# Ice-LogicDeck1.net
KiCad netlist of a schematic drawn in EAGLE
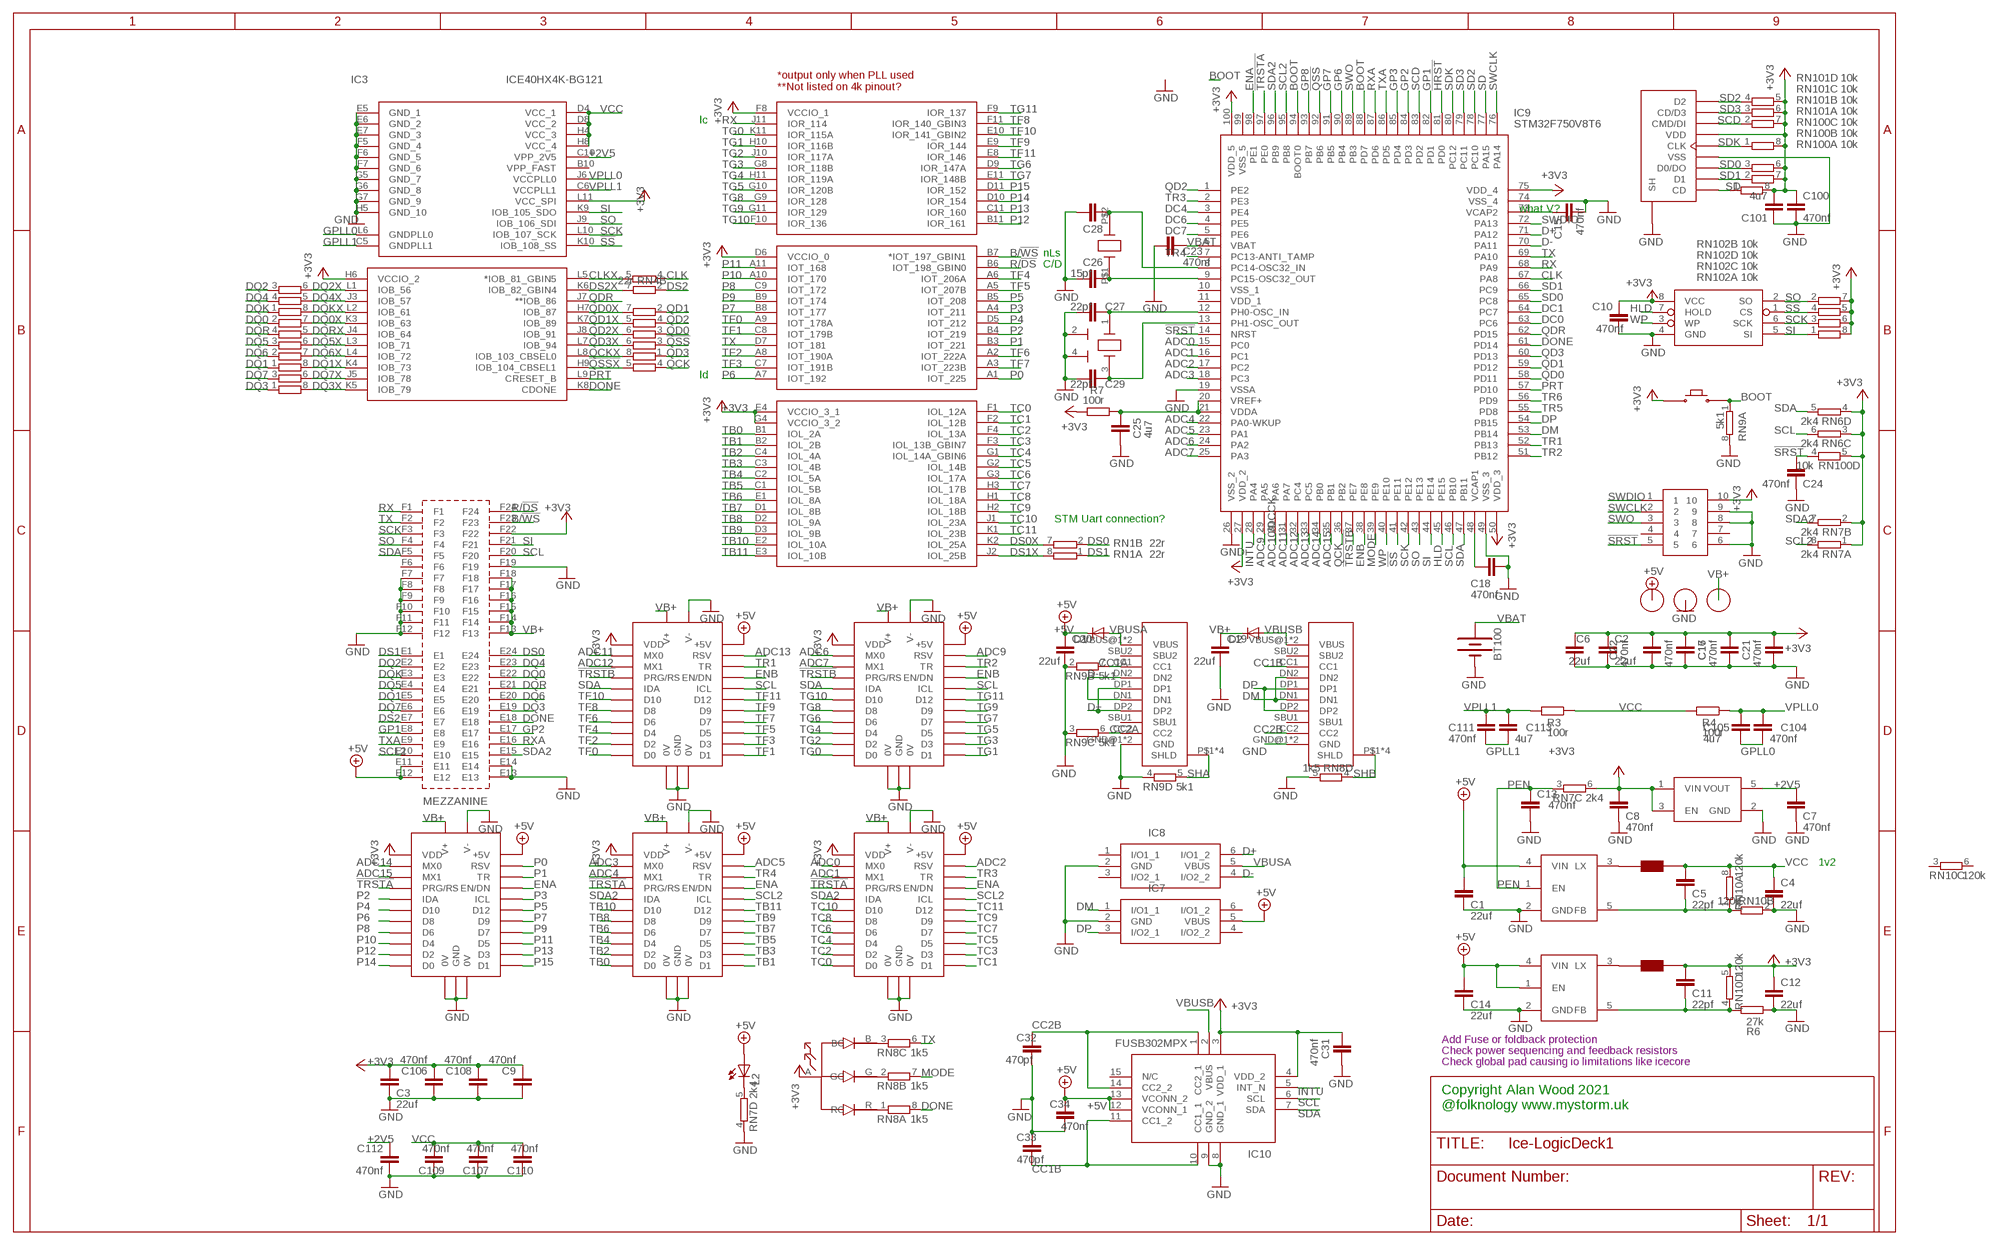
[diagram p0: schematic, sheet 1]

(export (version "E")
  (design (tool "Eeschema 10.0.6"))
  (components
    (comp (ref "BT100")
      (value "BATTERY-20MM_SMD")
      (footprint "eagle-import:BATTCON_20MM")
      (libsource (lib "eagle-import") (part "BATTERY-20MM_SMD"))
    )
    (comp (ref "C1")
      (value "22uf")
      (footprint "eagle-import:C0603")
      (libsource (lib "eagle-import") (part "C-EUC0603"))
    )
    (comp (ref "C2")
      (value "22uf")
      (footprint "eagle-import:C0603")
      (libsource (lib "eagle-import") (part "C-EUC0603"))
    )
    (comp (ref "C3")
      (value "22uf")
      (footprint "eagle-import:C0603")
      (libsource (lib "eagle-import") (part "C-EUC0603"))
    )
    (comp (ref "C4")
      (value "22uf")
      (footprint "eagle-import:C0603")
      (libsource (lib "eagle-import") (part "C-EUC0603"))
    )
    (comp (ref "C5")
      (value "22pf")
      (footprint "eagle-import:C0402")
      (libsource (lib "eagle-import") (part "C-EUC0402"))
    )
    (comp (ref "C6")
      (value "22uf")
      (footprint "eagle-import:C0603")
      (libsource (lib "eagle-import") (part "C-EUC0603"))
    )
    (comp (ref "C7")
      (value "470nf")
      (footprint "eagle-import:C0402")
      (libsource (lib "eagle-import") (part "C-EUC0402"))
    )
    (comp (ref "C8")
      (value "470nf")
      (footprint "eagle-import:C0402")
      (libsource (lib "eagle-import") (part "C-EUC0402"))
    )
    (comp (ref "C9")
      (value "470nf")
      (footprint "eagle-import:C0402")
      (libsource (lib "eagle-import") (part "C-EUC0402"))
    )
    (comp (ref "C10")
      (value "470nf")
      (footprint "eagle-import:C0402")
      (libsource (lib "eagle-import") (part "C-EUC0402"))
    )
    (comp (ref "C11")
      (value "22pf")
      (footprint "eagle-import:C0402")
      (libsource (lib "eagle-import") (part "C-EUC0402"))
    )
    (comp (ref "C12")
      (value "22uf")
      (footprint "eagle-import:C0603")
      (libsource (lib "eagle-import") (part "C-EUC0603"))
    )
    (comp (ref "C13")
      (value "470nf")
      (footprint "eagle-import:C0402")
      (libsource (lib "eagle-import") (part "C-EUC0402"))
    )
    (comp (ref "C14")
      (value "22uf")
      (footprint "eagle-import:C0603")
      (libsource (lib "eagle-import") (part "C-EUC0603"))
    )
    (comp (ref "C15")
      (value "470nf")
      (footprint "eagle-import:C0402")
      (libsource (lib "eagle-import") (part "C-EUC0402"))
    )
    (comp (ref "C16")
      (value "470nf")
      (footprint "eagle-import:C0402")
      (libsource (lib "eagle-import") (part "C-EUC0402"))
    )
    (comp (ref "C17")
      (value "470nf")
      (footprint "eagle-import:C0402")
      (libsource (lib "eagle-import") (part "C-EUC0402"))
    )
    (comp (ref "C18")
      (value "470nf")
      (footprint "eagle-import:C0402")
      (libsource (lib "eagle-import") (part "C-EUC0402"))
    )
    (comp (ref "C19")
      (value "22uf")
      (footprint "eagle-import:C0603")
      (libsource (lib "eagle-import") (part "C-EUC0603"))
    )
    (comp (ref "C20")
      (value "22uf")
      (footprint "eagle-import:C0603")
      (libsource (lib "eagle-import") (part "C-EUC0603"))
    )
    (comp (ref "C21")
      (value "470nf")
      (footprint "eagle-import:C0402")
      (libsource (lib "eagle-import") (part "C-EUC0402"))
    )
    (comp (ref "C22")
      (value "470nf")
      (footprint "eagle-import:C0402")
      (libsource (lib "eagle-import") (part "C-EUC0402"))
    )
    (comp (ref "C23")
      (value "470nf")
      (footprint "eagle-import:C0402")
      (libsource (lib "eagle-import") (part "C-EUC0402"))
    )
    (comp (ref "C24")
      (value "470nf")
      (footprint "eagle-import:C0402")
      (libsource (lib "eagle-import") (part "C-EUC0402"))
    )
    (comp (ref "C25")
      (value "4u7")
      (footprint "eagle-import:C0402")
      (libsource (lib "eagle-import") (part "C-EUC0402"))
    )
    (comp (ref "C26")
      (value "15pf")
      (footprint "eagle-import:C0402")
      (libsource (lib "eagle-import") (part "C-EUC0402"))
    )
    (comp (ref "C27")
      (value "22pf")
      (footprint "eagle-import:C0402")
      (libsource (lib "eagle-import") (part "C-EUC0402"))
    )
    (comp (ref "C28")
      (value "15pf")
      (footprint "eagle-import:C0402")
      (libsource (lib "eagle-import") (part "C-EUC0402"))
    )
    (comp (ref "C29")
      (value "22pf")
      (footprint "eagle-import:C0402")
      (libsource (lib "eagle-import") (part "C-EUC0402"))
    )
    (comp (ref "C31")
      (value "470nf")
      (footprint "eagle-import:C0402")
      (libsource (lib "eagle-import") (part "C-EUC0402"))
    )
    (comp (ref "C32")
      (value "470pf")
      (footprint "eagle-import:C0402")
      (libsource (lib "eagle-import") (part "C-EUC0402"))
    )
    (comp (ref "C33")
      (value "470pf")
      (footprint "eagle-import:C0402")
      (libsource (lib "eagle-import") (part "C-EUC0402"))
    )
    (comp (ref "C34")
      (value "470nf")
      (footprint "eagle-import:C0402")
      (libsource (lib "eagle-import") (part "C-EUC0402"))
    )
    (comp (ref "C100")
      (value "470nf")
      (footprint "eagle-import:C0402")
      (libsource (lib "eagle-import") (part "C-EUC0402"))
    )
    (comp (ref "C101")
      (value "4u7")
      (footprint "eagle-import:C0402")
      (libsource (lib "eagle-import") (part "C-EUC0402"))
    )
    (comp (ref "C104")
      (value "470nf")
      (footprint "eagle-import:C0402")
      (libsource (lib "eagle-import") (part "C-EUC0402"))
    )
    (comp (ref "C105")
      (value "4u7")
      (footprint "eagle-import:C0402")
      (libsource (lib "eagle-import") (part "C-EUC0402"))
    )
    (comp (ref "C106")
      (value "470nf")
      (footprint "eagle-import:C0402")
      (libsource (lib "eagle-import") (part "C-EUC0402"))
    )
    (comp (ref "C107")
      (value "470nf")
      (footprint "eagle-import:C0402")
      (libsource (lib "eagle-import") (part "C-EUC0402"))
    )
    (comp (ref "C108")
      (value "470nf")
      (footprint "eagle-import:C0402")
      (libsource (lib "eagle-import") (part "C-EUC0402"))
    )
    (comp (ref "C109")
      (value "470nf")
      (footprint "eagle-import:C0402")
      (libsource (lib "eagle-import") (part "C-EUC0402"))
    )
    (comp (ref "C110")
      (value "470nf")
      (footprint "eagle-import:C0402")
      (libsource (lib "eagle-import") (part "C-EUC0402"))
    )
    (comp (ref "C111")
      (value "470nf")
      (footprint "eagle-import:C0402")
      (libsource (lib "eagle-import") (part "C-EUC0402"))
    )
    (comp (ref "C112")
      (value "470nf")
      (footprint "eagle-import:C0402")
      (libsource (lib "eagle-import") (part "C-EUC0402"))
    )
    (comp (ref "C113")
      (value "4u7")
      (footprint "eagle-import:C0402")
      (libsource (lib "eagle-import") (part "C-EUC0402"))
    )
    (comp (ref "CN1")
      (value "USB-C-16")
      (footprint "eagle-import:USB-C")
      (libsource (lib "eagle-import") (part "USB-C-16"))
    )
    (comp (ref "CN2")
      (value "USB-C-16")
      (footprint "eagle-import:USB-C")
      (libsource (lib "eagle-import") (part "USB-C-16"))
    )
    (comp (ref "CN3")
      (value "2X5-HEADER")
      (footprint "eagle-import:1.27-2X5-HEADER")
      (libsource (lib "eagle-import") (part "2X5-HEADER"))
    )
    (comp (ref "D1")
      (value "DIODE-SOD123")
      (footprint "eagle-import:SOD123")
      (libsource (lib "eagle-import") (part "DIODE-SOD123"))
    )
    (comp (ref "D2")
      (value "DIODE-SOD123")
      (footprint "eagle-import:SOD123")
      (libsource (lib "eagle-import") (part "DIODE-SOD123"))
    )
    (comp (ref "DFU")
      (value "4X3-RA-BUTTON")
      (footprint "eagle-import:4X3-RA-BUTTON")
      (libsource (lib "eagle-import") (part "4X3-RA-BUTTON"))
    )
    (comp (ref "H1")
      (value "HOLE2.5MM-LARGE")
      (footprint "eagle-import:2M5-LARGE")
      (libsource (lib "eagle-import") (part "HOLE2.5MM-LARGE"))
    )
    (comp (ref "H3")
      (value "HOLE2.5MM-LARGE")
      (footprint "eagle-import:2M5-LARGE")
      (libsource (lib "eagle-import") (part "HOLE2.5MM-LARGE"))
    )
    (comp (ref "H4")
      (value "HOLE2.5MM-LARGE")
      (footprint "eagle-import:2M5-LARGE")
      (libsource (lib "eagle-import") (part "HOLE2.5MM-LARGE"))
    )
    (comp (ref "I1")
      (value "NRS4018")
      (footprint "eagle-import:NRC4018")
      (libsource (lib "eagle-import") (part "NRS4018"))
    )
    (comp (ref "I2")
      (value "NRS4018")
      (footprint "eagle-import:NRC4018")
      (libsource (lib "eagle-import") (part "NRS4018"))
    )
    (comp (ref "IC1")
      (value "AP3429/A")
      (footprint "eagle-import:TSOP-5_SOT23-5")
      (libsource (lib "eagle-import") (part "AP3429/A"))
    )
    (comp (ref "IC2")
      (value "NCP114")
      (footprint "eagle-import:TSOP-5_SOT23-5")
      (libsource (lib "eagle-import") (part "NCP114"))
    )
    (comp (ref "IC3")
      (value "ICE40HX4K-BG121")
      (footprint "eagle-import:BGA121C80P11X11_900X900X110")
      (fields (field (name "MOUSER_PART_NUMBER") "842-ICE40HX4K-BG121"))
      (libsource (lib "eagle-import") (part "ICE40HX4K-BG121"))
    )
    (comp (ref "IC4")
      (value "AT25SDF041A")
      (footprint "eagle-import:SOIC-8-NARROW")
      (libsource (lib "eagle-import") (part "AT25SDF041A"))
    )
    (comp (ref "IC5")
      (value "AP3429/A")
      (footprint "eagle-import:TSOP-5_SOT23-5")
      (libsource (lib "eagle-import") (part "AP3429/A"))
    )
    (comp (ref "IC7")
      (value "USBLC6-2SC6")
      (footprint "eagle-import:SOT95P280X145-6N")
      (fields (field (name "MOUSER_PART_NUMBER") "511-USBLC6-2SC6"))
      (libsource (lib "eagle-import") (part "USBLC6-2SC6"))
    )
    (comp (ref "IC8")
      (value "USBLC6-2SC6")
      (footprint "eagle-import:SOT95P280X145-6N")
      (fields (field (name "MOUSER_PART_NUMBER") "511-USBLC6-2SC6"))
      (libsource (lib "eagle-import") (part "USBLC6-2SC6"))
    )
    (comp (ref "IC9")
      (value "STM32F750V8T6")
      (footprint "eagle-import:QFP50P1600X1600X160-100N")
      (fields (field (name "MOUSER_PART_NUMBER") "511-STM32F750V8T6"))
      (libsource (lib "eagle-import") (part "STM32F750V8T6"))
    )
    (comp (ref "IC10")
      (value "FUSB302MPX")
      (footprint "eagle-import:QFN50P250X250X80-15N")
      (fields (field (name "MOUSER_PART_NUMBER") "512-FUSB302MPX"))
      (libsource (lib "eagle-import") (part "FUSB302MPX"))
    )
    (comp (ref "L1")
      (value "RGB_LED")
      (footprint "eagle-import:RGB_LED_IMM")
      (libsource (lib "eagle-import") (part "RGB_LED"))
    )
    (comp (ref "L2")
      (value "LEDCHIPLED_0805")
      (footprint "eagle-import:CHIPLED_0805")
      (libsource (lib "eagle-import") (part "LEDCHIPLED_0805"))
    )
    (comp (ref "MEZZANINE")
      (value "HYPER-TILECARRIER")
      (footprint "eagle-import:HYPER-TILE")
      (libsource (lib "eagle-import") (part "HYPER-TILECARRIER"))
    )
    (comp (ref "R3")
      (value "100r")
      (footprint "eagle-import:R0402")
      (libsource (lib "eagle-import") (part "R-EU_R0402"))
    )
    (comp (ref "R4")
      (value "100r")
      (footprint "eagle-import:R0402")
      (libsource (lib "eagle-import") (part "R-EU_R0402"))
    )
    (comp (ref "R6")
      (value "27k")
      (footprint "eagle-import:R0402")
      (libsource (lib "eagle-import") (part "R-EU_R0402"))
    )
    (comp (ref "R7")
      (value "100r")
      (footprint "eagle-import:R0402")
      (libsource (lib "eagle-import") (part "R-EU_R0402"))
    )
    (comp (ref "RN1")
      (value "22r")
      (footprint "eagle-import:EXB38V")
      (libsource (lib "eagle-import") (part "4R-NEXB38V"))
    )
    (comp (ref "RN2")
      (value "22r")
      (footprint "eagle-import:EXB38V")
      (libsource (lib "eagle-import") (part "4R-NEXB38V"))
    )
    (comp (ref "RN3")
      (value "22r")
      (footprint "eagle-import:EXB38V")
      (libsource (lib "eagle-import") (part "4R-NEXB38V"))
    )
    (comp (ref "RN4")
      (value "22r")
      (footprint "eagle-import:EXB38V")
      (libsource (lib "eagle-import") (part "4R-NEXB38V"))
    )
    (comp (ref "RN5")
      (value "22r")
      (footprint "eagle-import:EXB38V")
      (libsource (lib "eagle-import") (part "4R-NEXB38V"))
    )
    (comp (ref "RN6")
      (value "2k4")
      (footprint "eagle-import:EXB38V")
      (libsource (lib "eagle-import") (part "4R-NEXB38V"))
    )
    (comp (ref "RN7")
      (value "2k4")
      (footprint "eagle-import:EXB38V")
      (libsource (lib "eagle-import") (part "4R-NEXB38V"))
    )
    (comp (ref "RN8")
      (value "1k5")
      (footprint "eagle-import:EXB38V")
      (libsource (lib "eagle-import") (part "4R-NEXB38V"))
    )
    (comp (ref "RN9")
      (value "5k1")
      (footprint "eagle-import:EXB38V")
      (libsource (lib "eagle-import") (part "4R-NEXB38V"))
    )
    (comp (ref "RN10")
      (value "120k")
      (footprint "eagle-import:EXB38V")
      (libsource (lib "eagle-import") (part "4R-NEXB38V"))
    )
    (comp (ref "RN100")
      (value "10k")
      (footprint "eagle-import:EXB38V")
      (libsource (lib "eagle-import") (part "4R-NEXB38V"))
    )
    (comp (ref "RN101")
      (value "10k")
      (footprint "eagle-import:EXB38V")
      (libsource (lib "eagle-import") (part "4R-NEXB38V"))
    )
    (comp (ref "RN102")
      (value "10k")
      (footprint "eagle-import:EXB38V")
      (libsource (lib "eagle-import") (part "4R-NEXB38V"))
    )
    (comp (ref "SD100")
      (value "TF-15X15")
      (footprint "eagle-import:SDCARD")
      (libsource (lib "eagle-import") (part "TF-15X15"))
    )
    (comp (ref "TILE1")
      (value "UTILE_LPCARRIER_SMD_MALE_1.27")
      (footprint "eagle-import:UTILE_LP")
      (libsource (lib "eagle-import") (part "UTILE_LPCARRIER_SMD_MALE_1.27"))
    )
    (comp (ref "TILE2")
      (value "UTILE_LPCARRIER_SMD_MALE_1.27")
      (footprint "eagle-import:UTILE_LP")
      (libsource (lib "eagle-import") (part "UTILE_LPCARRIER_SMD_MALE_1.27"))
    )
    (comp (ref "TILE3")
      (value "UTILE_LPCARRIER_SMD_MALE_1.27")
      (footprint "eagle-import:UTILE_LP")
      (libsource (lib "eagle-import") (part "UTILE_LPCARRIER_SMD_MALE_1.27"))
    )
    (comp (ref "TILE4")
      (value "UTILE_LPCARRIER_SMD_MALE_1.27")
      (footprint "eagle-import:UTILE_LP")
      (libsource (lib "eagle-import") (part "UTILE_LPCARRIER_SMD_MALE_1.27"))
    )
    (comp (ref "TILE5")
      (value "UTILE_LPCARRIER_SMD_MALE_1.27")
      (footprint "eagle-import:UTILE_LP")
      (libsource (lib "eagle-import") (part "UTILE_LPCARRIER_SMD_MALE_1.27"))
    )
    (comp (ref "Y1")
      (value "12MZ")
      (footprint "eagle-import:CRYSTAL-3.2X2.5")
      (libsource (lib "eagle-import") (part "7M-25"))
    )
    (comp (ref "Y2")
      (value "FC-135")
      (footprint "eagle-import:FC135")
      (libsource (lib "eagle-import") (part "FC-135"))
    )
  )
  (nets
    (net (code "1") (name "+3V3") (class "Default")
      (node (ref "C10") (pin "1") (pinfunction "1_1") (pintype "passive"))
      (node (ref "C100") (pin "1") (pinfunction "1_1") (pintype "passive"))
      (node (ref "C101") (pin "2") (pinfunction "2_2") (pintype "passive"))
      (node (ref "C106") (pin "1") (pinfunction "1_1") (pintype "passive"))
      (node (ref "C108") (pin "1") (pinfunction "1_1") (pintype "passive"))
      (node (ref "C11") (pin "2") (pinfunction "2_2") (pintype "passive"))
      (node (ref "C12") (pin "1") (pinfunction "1_1") (pintype "passive"))
      (node (ref "C16") (pin "2") (pinfunction "2_2") (pintype "passive"))
      (node (ref "C17") (pin "2") (pinfunction "2_2") (pintype "passive"))
      (node (ref "C2") (pin "1") (pinfunction "1_1") (pintype "passive"))
      (node (ref "C21") (pin "2") (pinfunction "2_2") (pintype "passive"))
      (node (ref "C22") (pin "2") (pinfunction "2_2") (pintype "passive"))
      (node (ref "C3") (pin "2") (pinfunction "2_2") (pintype "passive"))
      (node (ref "C31") (pin "2") (pinfunction "2_2") (pintype "passive"))
      (node (ref "C6") (pin "2") (pinfunction "2_2") (pintype "passive"))
      (node (ref "C8") (pin "2") (pinfunction "2_2") (pintype "passive"))
      (node (ref "C9") (pin "1") (pinfunction "1_1") (pintype "passive"))
      (node (ref "CN3") (pin "10") (pinfunction "10_10") (pintype "bidirectional"))
      (node (ref "DFU") (pin "P$1") (pinfunction "P$1_P$1") (pintype "passive"))
      (node (ref "I2") (pin "P$2") (pinfunction "P$2_P$2") (pintype "passive"))
      (node (ref "IC10") (pin "3") (pinfunction "VDD_1_3") (pintype "bidirectional"))
      (node (ref "IC10") (pin "4") (pinfunction "VDD_2_4") (pintype "bidirectional"))
      (node (ref "IC2") (pin "1") (pinfunction "VIN_1") (pintype "power_in"))
      (node (ref "IC2") (pin "3") (pinfunction "EN_3") (pintype "input"))
      (node (ref "IC3") (pin "D6") (pinfunction "VCCIO_0_D6") (pintype "bidirectional"))
      (node (ref "IC3") (pin "E4") (pinfunction "VCCIO_3_1_E4") (pintype "bidirectional"))
      (node (ref "IC3") (pin "F8") (pinfunction "VCCIO_1_F8") (pintype "bidirectional"))
      (node (ref "IC3") (pin "G4") (pinfunction "VCCIO_3_2_G4") (pintype "bidirectional"))
      (node (ref "IC3") (pin "H6") (pinfunction "VCCIO_2_H6") (pintype "bidirectional"))
      (node (ref "IC3") (pin "L11") (pinfunction "VCC_SPI_L11") (pintype "bidirectional"))
      (node (ref "IC4") (pin "8") (pinfunction "VCC_8") (pintype "power_in"))
      (node (ref "IC9") (pin "100") (pinfunction "VDD_5_100") (pintype "bidirectional"))
      (node (ref "IC9") (pin "27") (pinfunction "VDD_2_27") (pintype "bidirectional"))
      (node (ref "IC9") (pin "50") (pinfunction "VDD_3_50") (pintype "bidirectional"))
      (node (ref "IC9") (pin "75") (pinfunction "VDD_4_75") (pintype "bidirectional"))
      (node (ref "L1") (pin "A") (pinfunction "ANODE_A") (pintype "bidirectional"))
      (node (ref "MEZZANINE") (pin "F22") (pinfunction "F22_F22") (pintype "bidirectional"))
      (node (ref "R7") (pin "2") (pinfunction "2_2") (pintype "passive"))
      (node (ref "RN10") (pin "5") (pinfunction "2_5") (pintype "passive"))
      (node (ref "RN100") (pin "5") (pinfunction "2_5") (pintype "passive"))
      (node (ref "RN100") (pin "6") (pinfunction "2_6") (pintype "passive"))
      (node (ref "RN100") (pin "7") (pinfunction "2_7") (pintype "passive"))
      (node (ref "RN100") (pin "8") (pinfunction "2_8") (pintype "passive"))
      (node (ref "RN101") (pin "5") (pinfunction "2_5") (pintype "passive"))
      (node (ref "RN101") (pin "6") (pinfunction "2_6") (pintype "passive"))
      (node (ref "RN101") (pin "7") (pinfunction "2_7") (pintype "passive"))
      (node (ref "RN101") (pin "8") (pinfunction "2_8") (pintype "passive"))
      (node (ref "RN102") (pin "5") (pinfunction "2_5") (pintype "passive"))
      (node (ref "RN102") (pin "6") (pinfunction "2_6") (pintype "passive"))
      (node (ref "RN102") (pin "7") (pinfunction "2_7") (pintype "passive"))
      (node (ref "RN102") (pin "8") (pinfunction "2_8") (pintype "passive"))
      (node (ref "RN6") (pin "3") (pinfunction "1_3") (pintype "passive"))
      (node (ref "RN6") (pin "4") (pinfunction "1_4") (pintype "passive"))
      (node (ref "RN7") (pin "1") (pinfunction "1_1") (pintype "passive"))
      (node (ref "RN7") (pin "2") (pinfunction "1_2") (pintype "passive"))
      (node (ref "RN7") (pin "6") (pinfunction "2_6") (pintype "passive"))
      (node (ref "SD100") (pin "P$6") (pinfunction "VDD_P$6") (pintype "power_in"))
      (node (ref "TILE1") (pin "P$18") (pinfunction "VDD_P$18") (pintype "power_in"))
      (node (ref "TILE2") (pin "P$18") (pinfunction "VDD_P$18") (pintype "power_in"))
      (node (ref "TILE3") (pin "P$18") (pinfunction "VDD_P$18") (pintype "power_in"))
      (node (ref "TILE4") (pin "P$18") (pinfunction "VDD_P$18") (pintype "power_in"))
      (node (ref "TILE5") (pin "P$18") (pinfunction "VDD_P$18") (pintype "power_in"))
    )
    (net (code "2") (name "+5V") (class "Default")
      (node (ref "C1") (pin "2") (pinfunction "2_2") (pintype "passive"))
      (node (ref "C14") (pin "2") (pinfunction "2_2") (pintype "passive"))
      (node (ref "C20") (pin "1") (pinfunction "1_1") (pintype "passive"))
      (node (ref "C34") (pin "2") (pinfunction "2_2") (pintype "passive"))
      (node (ref "D1") (pin "C") (pinfunction "C_C") (pintype "passive"))
      (node (ref "H1") (pin "P$1") (pinfunction "P_P$1") (pintype "bidirectional"))
      (node (ref "IC1") (pin "4") (pinfunction "VIN_4") (pintype "power_in"))
      (node (ref "IC10") (pin "12") (pinfunction "VCONN_1_12") (pintype "bidirectional"))
      (node (ref "IC10") (pin "13") (pinfunction "VCONN_2_13") (pintype "bidirectional"))
      (node (ref "IC5") (pin "1") (pinfunction "EN_1") (pintype "input"))
      (node (ref "IC5") (pin "4") (pinfunction "VIN_4") (pintype "power_in"))
      (node (ref "IC7") (pin "5") (pinfunction "VBUS_5") (pintype "bidirectional"))
      (node (ref "L2") (pin "A") (pinfunction "A_A") (pintype "passive"))
      (node (ref "MEZZANINE") (pin "E11") (pinfunction "E11_E11") (pintype "bidirectional"))
      (node (ref "MEZZANINE") (pin "E12") (pinfunction "E12_E12") (pintype "bidirectional"))
      (node (ref "TILE1") (pin "P$43") (pinfunction "+5V_P$43") (pintype "power_in"))
      (node (ref "TILE2") (pin "P$43") (pinfunction "+5V_P$43") (pintype "power_in"))
      (node (ref "TILE3") (pin "P$43") (pinfunction "+5V_P$43") (pintype "power_in"))
      (node (ref "TILE4") (pin "P$43") (pinfunction "+5V_P$43") (pintype "power_in"))
      (node (ref "TILE5") (pin "P$43") (pinfunction "+5V_P$43") (pintype "power_in"))
    )
    (net (code "3") (name "/+2V5") (class "Default")
      (node (ref "C112") (pin "1") (pinfunction "1_1") (pintype "passive"))
      (node (ref "C7") (pin "2") (pinfunction "2_2") (pintype "passive"))
      (node (ref "IC2") (pin "5") (pinfunction "VOUT_5") (pintype "power_in"))
      (node (ref "IC3") (pin "C10") (pinfunction "VPP_2V5_C10") (pintype "bidirectional"))
    )
    (net (code "4") (name "/ADC0") (class "Default")
      (node (ref "IC9") (pin "15") (pinfunction "PC0_15") (pintype "bidirectional"))
      (node (ref "TILE4") (pin "P$17") (pinfunction "MX0_P$17") (pintype "bidirectional"))
    )
    (net (code "5") (name "/ADC1") (class "Default")
      (node (ref "IC9") (pin "16") (pinfunction "PC1_16") (pintype "bidirectional"))
      (node (ref "TILE4") (pin "P$16") (pinfunction "MX1_P$16") (pintype "bidirectional"))
    )
    (net (code "6") (name "/ADC2") (class "Default")
      (node (ref "IC9") (pin "17") (pinfunction "PC2_17") (pintype "bidirectional"))
      (node (ref "TILE4") (pin "P$42") (pinfunction "RSV_P$42") (pintype "bidirectional"))
    )
    (net (code "7") (name "/ADC3") (class "Default")
      (node (ref "IC9") (pin "18") (pinfunction "PC3_18") (pintype "bidirectional"))
      (node (ref "TILE1") (pin "P$17") (pinfunction "MX0_P$17") (pintype "bidirectional"))
    )
    (net (code "8") (name "/ADC4") (class "Default")
      (node (ref "IC9") (pin "22") (pinfunction "PA0-WKUP_22") (pintype "bidirectional"))
      (node (ref "TILE1") (pin "P$16") (pinfunction "MX1_P$16") (pintype "bidirectional"))
    )
    (net (code "9") (name "/ADC5") (class "Default")
      (node (ref "IC9") (pin "23") (pinfunction "PA1_23") (pintype "bidirectional"))
      (node (ref "TILE1") (pin "P$42") (pinfunction "RSV_P$42") (pintype "bidirectional"))
    )
    (net (code "10") (name "/ADC6") (class "Default")
      (node (ref "IC9") (pin "24") (pinfunction "PA2_24") (pintype "bidirectional"))
      (node (ref "TILE5") (pin "P$17") (pinfunction "MX0_P$17") (pintype "bidirectional"))
    )
    (net (code "11") (name "/ADC7") (class "Default")
      (node (ref "IC9") (pin "25") (pinfunction "PA3_25") (pintype "bidirectional"))
      (node (ref "TILE5") (pin "P$16") (pinfunction "MX1_P$16") (pintype "bidirectional"))
    )
    (net (code "12") (name "/ADC9") (class "Default")
      (node (ref "IC9") (pin "29") (pinfunction "PA5_29") (pintype "bidirectional"))
      (node (ref "TILE5") (pin "P$42") (pinfunction "RSV_P$42") (pintype "bidirectional"))
    )
    (net (code "13") (name "/ADC10{slash}DCCK") (class "Default")
      (node (ref "IC9") (pin "30") (pinfunction "PA6_30") (pintype "bidirectional"))
    )
    (net (code "14") (name "/ADC11") (class "Default")
      (node (ref "IC9") (pin "31") (pinfunction "PA7_31") (pintype "bidirectional"))
      (node (ref "TILE3") (pin "P$17") (pinfunction "MX0_P$17") (pintype "bidirectional"))
    )
    (net (code "15") (name "/ADC12") (class "Default")
      (node (ref "IC9") (pin "32") (pinfunction "PC4_32") (pintype "bidirectional"))
      (node (ref "TILE3") (pin "P$16") (pinfunction "MX1_P$16") (pintype "bidirectional"))
    )
    (net (code "16") (name "/ADC13") (class "Default")
      (node (ref "IC9") (pin "33") (pinfunction "PC5_33") (pintype "bidirectional"))
      (node (ref "TILE3") (pin "P$42") (pinfunction "RSV_P$42") (pintype "bidirectional"))
    )
    (net (code "17") (name "/ADC14") (class "Default")
      (node (ref "IC9") (pin "34") (pinfunction "PB0_34") (pintype "bidirectional"))
      (node (ref "TILE2") (pin "P$17") (pinfunction "MX0_P$17") (pintype "bidirectional"))
    )
    (net (code "18") (name "/ADC15") (class "Default")
      (node (ref "IC9") (pin "35") (pinfunction "PB1_35") (pintype "bidirectional"))
      (node (ref "TILE2") (pin "P$16") (pinfunction "MX1_P$16") (pintype "bidirectional"))
    )
    (net (code "19") (name "/BOOT") (class "Default")
      (node (ref "DFU") (pin "P$2") (pinfunction "P$2_P$2") (pintype "passive"))
      (node (ref "IC9") (pin "88") (pinfunction "PD7_88") (pintype "bidirectional"))
      (node (ref "IC9") (pin "94") (pinfunction "BOOT0_94") (pintype "bidirectional"))
      (node (ref "RN9") (pin "1") (pinfunction "1_1") (pintype "passive"))
    )
    (net (code "20") (name "/B{slash}~{WS}") (class "Default")
      (node (ref "IC3") (pin "B7") (pinfunction "*IOT_197_GBIN1_B7") (pintype "bidirectional"))
      (node (ref "MEZZANINE") (pin "F23") (pinfunction "F23_F23") (pintype "bidirectional"))
    )
    (net (code "21") (name "/CC1A") (class "Default")
      (node (ref "CN1") (pin "CC1") (pinfunction "CC1_CC1") (pintype "bidirectional"))
      (node (ref "RN9") (pin "7") (pinfunction "2_7") (pintype "passive"))
    )
    (net (code "22") (name "/CC1B") (class "Default")
      (node (ref "C33") (pin "1") (pinfunction "1_1") (pintype "passive"))
      (node (ref "CN2") (pin "CC1") (pinfunction "CC1_CC1") (pintype "bidirectional"))
      (node (ref "IC10") (pin "10") (pinfunction "CC1_1_10") (pintype "bidirectional"))
      (node (ref "IC10") (pin "11") (pinfunction "CC1_2_11") (pintype "bidirectional"))
    )
    (net (code "23") (name "/CC2A") (class "Default")
      (node (ref "CN1") (pin "CC2") (pinfunction "CC2_CC2") (pintype "bidirectional"))
      (node (ref "RN9") (pin "6") (pinfunction "2_6") (pintype "passive"))
    )
    (net (code "24") (name "/CC2B") (class "Default")
      (node (ref "C32") (pin "2") (pinfunction "2_2") (pintype "passive"))
      (node (ref "CN2") (pin "CC2") (pinfunction "CC2_CC2") (pintype "bidirectional"))
      (node (ref "IC10") (pin "1") (pinfunction "CC2_1_1") (pintype "bidirectional"))
      (node (ref "IC10") (pin "14") (pinfunction "CC2_2_14") (pintype "bidirectional"))
    )
    (net (code "25") (name "/CLK") (class "Default")
      (node (ref "IC9") (pin "67") (pinfunction "PA8_67") (pintype "bidirectional"))
      (node (ref "RN3") (pin "4") (pinfunction "1_4") (pintype "passive"))
    )
    (net (code "26") (name "/CLKX") (class "Default")
      (node (ref "IC3") (pin "L5") (pinfunction "*IOB_81_GBIN5_L5") (pintype "bidirectional"))
      (node (ref "RN3") (pin "5") (pinfunction "2_5") (pintype "passive"))
    )
    (net (code "27") (name "/D+") (class "Default")
      (node (ref "CN1") (pin "DP1") (pinfunction "DP1_DP1") (pintype "bidirectional"))
      (node (ref "CN1") (pin "DP2") (pinfunction "DP2_DP2") (pintype "bidirectional"))
      (node (ref "IC8") (pin "6") (pinfunction "I/O1_2_6") (pintype "bidirectional"))
      (node (ref "IC9") (pin "71") (pinfunction "PA12_71") (pintype "bidirectional"))
    )
    (net (code "28") (name "/D-") (class "Default")
      (node (ref "CN1") (pin "DN1") (pinfunction "DN1_DN1") (pintype "bidirectional"))
      (node (ref "CN1") (pin "DN2") (pinfunction "DN2_DN2") (pintype "bidirectional"))
      (node (ref "IC8") (pin "4") (pinfunction "I/O2_2_4") (pintype "bidirectional"))
      (node (ref "IC9") (pin "70") (pinfunction "PA11_70") (pintype "bidirectional"))
    )
    (net (code "29") (name "/DC0") (class "Default")
      (node (ref "IC9") (pin "63") (pinfunction "PC6_63") (pintype "bidirectional"))
    )
    (net (code "30") (name "/DC1") (class "Default")
      (node (ref "IC9") (pin "64") (pinfunction "PC7_64") (pintype "bidirectional"))
    )
    (net (code "31") (name "/DC4") (class "Default")
      (node (ref "IC9") (pin "3") (pinfunction "PE4_3") (pintype "bidirectional"))
    )
    (net (code "32") (name "/DC6") (class "Default")
      (node (ref "IC9") (pin "4") (pinfunction "PE5_4") (pintype "bidirectional"))
    )
    (net (code "33") (name "/DC7") (class "Default")
      (node (ref "IC9") (pin "5") (pinfunction "PE6_5") (pintype "bidirectional"))
    )
    (net (code "34") (name "/DM") (class "Default")
      (node (ref "CN2") (pin "DN1") (pinfunction "DN1_DN1") (pintype "bidirectional"))
      (node (ref "CN2") (pin "DN2") (pinfunction "DN2_DN2") (pintype "bidirectional"))
      (node (ref "IC7") (pin "1") (pinfunction "I/O1_1_1") (pintype "bidirectional"))
      (node (ref "IC9") (pin "53") (pinfunction "PB14_53") (pintype "bidirectional"))
    )
    (net (code "35") (name "/DONE") (class "Default")
      (node (ref "IC3") (pin "K8") (pinfunction "CDONE_K8") (pintype "bidirectional"))
      (node (ref "IC9") (pin "61") (pinfunction "PD14_61") (pintype "bidirectional"))
      (node (ref "MEZZANINE") (pin "E18") (pinfunction "E18_E18") (pintype "bidirectional"))
      (node (ref "RN8") (pin "8") (pinfunction "2_8") (pintype "passive"))
    )
    (net (code "36") (name "/DP") (class "Default")
      (node (ref "CN2") (pin "DP1") (pinfunction "DP1_DP1") (pintype "bidirectional"))
      (node (ref "CN2") (pin "DP2") (pinfunction "DP2_DP2") (pintype "bidirectional"))
      (node (ref "IC7") (pin "3") (pinfunction "I/O2_1_3") (pintype "bidirectional"))
      (node (ref "IC9") (pin "54") (pinfunction "PB15_54") (pintype "bidirectional"))
    )
    (net (code "37") (name "/DQ0") (class "Default")
      (node (ref "MEZZANINE") (pin "E22") (pinfunction "E22_E22") (pintype "bidirectional"))
      (node (ref "RN2") (pin "2") (pinfunction "1_2") (pintype "passive"))
    )
    (net (code "38") (name "/DQ0X") (class "Default")
      (node (ref "IC3") (pin "K3") (pinfunction "IOB_63_K3") (pintype "bidirectional"))
      (node (ref "RN2") (pin "7") (pinfunction "2_7") (pintype "passive"))
    )
    (net (code "39") (name "/DQ1") (class "Default")
      (node (ref "MEZZANINE") (pin "E5") (pinfunction "E5_E5") (pintype "bidirectional"))
      (node (ref "RN3") (pin "1") (pinfunction "1_1") (pintype "passive"))
    )
    (net (code "40") (name "/DQ1X") (class "Default")
      (node (ref "IC3") (pin "K4") (pinfunction "IOB_73_K4") (pintype "bidirectional"))
      (node (ref "RN3") (pin "8") (pinfunction "2_8") (pintype "passive"))
    )
    (net (code "41") (name "/DQ2") (class "Default")
      (node (ref "MEZZANINE") (pin "E2") (pinfunction "E2_E2") (pintype "bidirectional"))
      (node (ref "RN1") (pin "3") (pinfunction "1_3") (pintype "passive"))
    )
    (net (code "42") (name "/DQ2X") (class "Default")
      (node (ref "IC3") (pin "L1") (pinfunction "IOB_56_L1") (pintype "bidirectional"))
      (node (ref "RN1") (pin "6") (pinfunction "2_6") (pintype "passive"))
    )
    (net (code "43") (name "/DQ3") (class "Default")
      (node (ref "MEZZANINE") (pin "E19") (pinfunction "E19_E19") (pintype "bidirectional"))
      (node (ref "RN4") (pin "1") (pinfunction "1_1") (pintype "passive"))
    )
    (net (code "44") (name "/DQ3X") (class "Default")
      (node (ref "IC3") (pin "K5") (pinfunction "IOB_79_K5") (pintype "bidirectional"))
      (node (ref "RN4") (pin "8") (pinfunction "2_8") (pintype "passive"))
    )
    (net (code "45") (name "/DQ4") (class "Default")
      (node (ref "MEZZANINE") (pin "E23") (pinfunction "E23_E23") (pintype "bidirectional"))
      (node (ref "RN1") (pin "4") (pinfunction "1_4") (pintype "passive"))
    )
    (net (code "46") (name "/DQ4X") (class "Default")
      (node (ref "IC3") (pin "J3") (pinfunction "IOB_57_J3") (pintype "bidirectional"))
      (node (ref "RN1") (pin "5") (pinfunction "2_5") (pintype "passive"))
    )
    (net (code "47") (name "/DQ5") (class "Default")
      (node (ref "MEZZANINE") (pin "E4") (pinfunction "E4_E4") (pintype "bidirectional"))
      (node (ref "RN2") (pin "3") (pinfunction "1_3") (pintype "passive"))
    )
    (net (code "48") (name "/DQ5X") (class "Default")
      (node (ref "IC3") (pin "L3") (pinfunction "IOB_71_L3") (pintype "bidirectional"))
      (node (ref "RN2") (pin "6") (pinfunction "2_6") (pintype "passive"))
    )
    (net (code "49") (name "/DQ6") (class "Default")
      (node (ref "MEZZANINE") (pin "E20") (pinfunction "E20_E20") (pintype "bidirectional"))
      (node (ref "RN3") (pin "2") (pinfunction "1_2") (pintype "passive"))
    )
    (net (code "50") (name "/DQ6X") (class "Default")
      (node (ref "IC3") (pin "L4") (pinfunction "IOB_72_L4") (pintype "bidirectional"))
      (node (ref "RN3") (pin "7") (pinfunction "2_7") (pintype "passive"))
    )
    (net (code "51") (name "/DQ7") (class "Default")
      (node (ref "MEZZANINE") (pin "E6") (pinfunction "E6_E6") (pintype "bidirectional"))
      (node (ref "RN3") (pin "3") (pinfunction "1_3") (pintype "passive"))
    )
    (net (code "52") (name "/DQ7X") (class "Default")
      (node (ref "IC3") (pin "J5") (pinfunction "IOB_78_J5") (pintype "bidirectional"))
      (node (ref "RN3") (pin "6") (pinfunction "2_6") (pintype "passive"))
    )
    (net (code "53") (name "/DQK") (class "Default")
      (node (ref "MEZZANINE") (pin "E3") (pinfunction "E3_E3") (pintype "bidirectional"))
      (node (ref "RN2") (pin "1") (pinfunction "1_1") (pintype "passive"))
    )
    (net (code "54") (name "/DQKX") (class "Default")
      (node (ref "IC3") (pin "L2") (pinfunction "IOB_61_L2") (pintype "bidirectional"))
      (node (ref "RN2") (pin "8") (pinfunction "2_8") (pintype "passive"))
    )
    (net (code "55") (name "/DQR") (class "Default")
      (node (ref "MEZZANINE") (pin "E21") (pinfunction "E21_E21") (pintype "bidirectional"))
      (node (ref "RN2") (pin "4") (pinfunction "1_4") (pintype "passive"))
    )
    (net (code "56") (name "/DQRX") (class "Default")
      (node (ref "IC3") (pin "J4") (pinfunction "IOB_64_J4") (pintype "bidirectional"))
      (node (ref "RN2") (pin "5") (pinfunction "2_5") (pintype "passive"))
    )
    (net (code "57") (name "/DS0") (class "Default")
      (node (ref "MEZZANINE") (pin "E24") (pinfunction "E24_E24") (pintype "bidirectional"))
      (node (ref "RN1") (pin "2") (pinfunction "1_2") (pintype "passive"))
    )
    (net (code "58") (name "/DS0X") (class "Default")
      (node (ref "IC3") (pin "K2") (pinfunction "IOL_25A_K2") (pintype "bidirectional"))
      (node (ref "RN1") (pin "7") (pinfunction "2_7") (pintype "passive"))
    )
    (net (code "59") (name "/DS1") (class "Default")
      (node (ref "MEZZANINE") (pin "E1") (pinfunction "E1_E1") (pintype "bidirectional"))
      (node (ref "RN1") (pin "1") (pinfunction "1_1") (pintype "passive"))
    )
    (net (code "60") (name "/DS1X") (class "Default")
      (node (ref "IC3") (pin "J2") (pinfunction "IOL_25B_J2") (pintype "bidirectional"))
      (node (ref "RN1") (pin "8") (pinfunction "2_8") (pintype "passive"))
    )
    (net (code "61") (name "/DS2") (class "Default")
      (node (ref "MEZZANINE") (pin "E7") (pinfunction "E7_E7") (pintype "bidirectional"))
      (node (ref "RN4") (pin "2") (pinfunction "1_2") (pintype "passive"))
    )
    (net (code "62") (name "/DS2X") (class "Default")
      (node (ref "IC3") (pin "K6") (pinfunction "IOB_82_GBIN4_K6") (pintype "bidirectional"))
      (node (ref "RN4") (pin "7") (pinfunction "2_7") (pintype "passive"))
    )
    (net (code "63") (name "/ENA") (class "Default")
      (node (ref "IC9") (pin "98") (pinfunction "PE1_98") (pintype "bidirectional"))
      (node (ref "TILE1") (pin "P$40") (pinfunction "EN/DN_P$40") (pintype "open_collector"))
      (node (ref "TILE2") (pin "P$40") (pinfunction "EN/DN_P$40") (pintype "open_collector"))
      (node (ref "TILE4") (pin "P$40") (pinfunction "EN/DN_P$40") (pintype "open_collector"))
    )
    (net (code "64") (name "/ENB") (class "Default")
      (node (ref "IC9") (pin "38") (pinfunction "PE8_38") (pintype "bidirectional"))
      (node (ref "TILE3") (pin "P$40") (pinfunction "EN/DN_P$40") (pintype "open_collector"))
      (node (ref "TILE5") (pin "P$40") (pinfunction "EN/DN_P$40") (pintype "open_collector"))
    )
    (net (code "65") (name "/GP1") (class "Default")
      (node (ref "IC9") (pin "82") (pinfunction "PD1_82") (pintype "bidirectional"))
      (node (ref "MEZZANINE") (pin "E8") (pinfunction "E8_E8") (pintype "bidirectional"))
    )
    (net (code "66") (name "/GP2") (class "Default")
      (node (ref "IC9") (pin "84") (pinfunction "PD3_84") (pintype "bidirectional"))
      (node (ref "MEZZANINE") (pin "E17") (pinfunction "E17_E17") (pintype "bidirectional"))
    )
    (net (code "67") (name "/GP3") (class "Default")
      (node (ref "IC9") (pin "85") (pinfunction "PD4_85") (pintype "bidirectional"))
    )
    (net (code "68") (name "/GP6") (class "Default")
      (node (ref "IC9") (pin "90") (pinfunction "PB4_90") (pintype "bidirectional"))
    )
    (net (code "69") (name "/GP7") (class "Default")
      (node (ref "IC9") (pin "91") (pinfunction "PB5_91") (pintype "bidirectional"))
    )
    (net (code "70") (name "/GP8") (class "Default")
      (node (ref "IC9") (pin "93") (pinfunction "PB7_93") (pintype "bidirectional"))
    )
    (net (code "71") (name "/GPLL0") (class "Default")
      (node (ref "C104") (pin "1") (pinfunction "1_1") (pintype "passive"))
      (node (ref "C105") (pin "1") (pinfunction "1_1") (pintype "passive"))
      (node (ref "IC3") (pin "L6") (pinfunction "GNDPLL0_L6") (pintype "bidirectional"))
    )
    (net (code "72") (name "/GPLL1") (class "Default")
      (node (ref "C111") (pin "1") (pinfunction "1_1") (pintype "passive"))
      (node (ref "C113") (pin "1") (pinfunction "1_1") (pintype "passive"))
      (node (ref "IC3") (pin "C5") (pinfunction "GNDPLL1_C5") (pintype "bidirectional"))
    )
    (net (code "73") (name "/HLD") (class "Default")
      (node (ref "IC4") (pin "7") (pinfunction "HOLD_7") (pintype "bidirectional"))
      (node (ref "IC9") (pin "45") (pinfunction "PE15_45") (pintype "bidirectional"))
    )
    (net (code "74") (name "/INTU") (class "Default")
      (node (ref "IC10") (pin "5") (pinfunction "INT_N_5") (pintype "bidirectional"))
      (node (ref "IC9") (pin "28") (pinfunction "PA4_28") (pintype "bidirectional"))
    )
    (net (code "75") (name "/MODE") (class "Default")
      (node (ref "IC9") (pin "39") (pinfunction "PE9_39") (pintype "bidirectional"))
      (node (ref "RN8") (pin "7") (pinfunction "2_7") (pintype "passive"))
    )
    (net (code "76") (name "/P0") (class "Default")
      (node (ref "IC3") (pin "A1") (pinfunction "IOT_225_A1") (pintype "bidirectional"))
      (node (ref "TILE2") (pin "P$42") (pinfunction "RSV_P$42") (pintype "bidirectional"))
    )
    (net (code "77") (name "/P1") (class "Default")
      (node (ref "IC3") (pin "B3") (pinfunction "IOT_221_B3") (pintype "bidirectional"))
      (node (ref "TILE2") (pin "P$41") (pinfunction "TR_P$41") (pintype "bidirectional"))
    )
    (net (code "78") (name "/P2") (class "Default")
      (node (ref "IC3") (pin "B4") (pinfunction "IOT_219_B4") (pintype "bidirectional"))
      (node (ref "TILE2") (pin "P$14") (pinfunction "IDA_P$14") (pintype "bidirectional"))
    )
    (net (code "79") (name "/P3") (class "Default")
      (node (ref "IC3") (pin "A4") (pinfunction "IOT_211_A4") (pintype "bidirectional"))
      (node (ref "TILE2") (pin "P$39") (pinfunction "ICL_P$39") (pintype "bidirectional"))
    )
    (net (code "80") (name "/P4") (class "Default")
      (node (ref "IC3") (pin "D5") (pinfunction "IOT_212_D5") (pintype "bidirectional"))
      (node (ref "TILE2") (pin "P$13") (pinfunction "D10_P$13") (pintype "bidirectional"))
    )
    (net (code "81") (name "/P5") (class "Default")
      (node (ref "IC3") (pin "B5") (pinfunction "IOT_208_B5") (pintype "bidirectional"))
      (node (ref "TILE2") (pin "P$38") (pinfunction "D12_P$38") (pintype "bidirectional"))
    )
    (net (code "82") (name "/P6") (class "Default")
      (node (ref "IC3") (pin "A7") (pinfunction "IOT_192_A7") (pintype "bidirectional"))
      (node (ref "TILE2") (pin "P$12") (pinfunction "D8_P$12") (pintype "bidirectional"))
    )
    (net (code "83") (name "/P7") (class "Default")
      (node (ref "IC3") (pin "B8") (pinfunction "IOT_177_B8") (pintype "bidirectional"))
      (node (ref "TILE2") (pin "P$37") (pinfunction "D9_P$37") (pintype "bidirectional"))
    )
    (net (code "84") (name "/P8") (class "Default")
      (node (ref "IC3") (pin "C9") (pinfunction "IOT_172_C9") (pintype "bidirectional"))
      (node (ref "TILE2") (pin "P$11") (pinfunction "D6_P$11") (pintype "bidirectional"))
    )
    (net (code "85") (name "/P9") (class "Default")
      (node (ref "IC3") (pin "B9") (pinfunction "IOT_174_B9") (pintype "bidirectional"))
      (node (ref "TILE2") (pin "P$36") (pinfunction "D7_P$36") (pintype "bidirectional"))
    )
    (net (code "86") (name "/P10") (class "Default")
      (node (ref "IC3") (pin "A10") (pinfunction "IOT_170_A10") (pintype "bidirectional"))
      (node (ref "TILE2") (pin "P$10") (pinfunction "D4_P$10") (pintype "bidirectional"))
    )
    (net (code "87") (name "/P11") (class "Default")
      (node (ref "IC3") (pin "A11") (pinfunction "IOT_168_A11") (pintype "bidirectional"))
      (node (ref "TILE2") (pin "P$35") (pinfunction "D5_P$35") (pintype "bidirectional"))
    )
    (net (code "88") (name "/P12") (class "Default")
      (node (ref "IC3") (pin "B11") (pinfunction "IOR_161_B11") (pintype "bidirectional"))
      (node (ref "TILE2") (pin "P$9") (pinfunction "D2_P$9") (pintype "bidirectional"))
    )
    (net (code "89") (name "/P13") (class "Default")
      (node (ref "IC3") (pin "C11") (pinfunction "IOR_160_C11") (pintype "bidirectional"))
      (node (ref "TILE2") (pin "P$34") (pinfunction "D3_P$34") (pintype "bidirectional"))
    )
    (net (code "90") (name "/P14") (class "Default")
      (node (ref "IC3") (pin "D10") (pinfunction "IOR_154_D10") (pintype "bidirectional"))
      (node (ref "TILE2") (pin "P$8") (pinfunction "D0_P$8") (pintype "bidirectional"))
    )
    (net (code "91") (name "/P15") (class "Default")
      (node (ref "IC3") (pin "D11") (pinfunction "IOR_152_D11") (pintype "bidirectional"))
      (node (ref "TILE2") (pin "P$33") (pinfunction "D1_P$33") (pintype "bidirectional"))
    )
    (net (code "92") (name "/PEN") (class "Default")
      (node (ref "C13") (pin "1") (pinfunction "1_1") (pintype "passive"))
      (node (ref "IC1") (pin "1") (pinfunction "EN_1") (pintype "input"))
      (node (ref "RN7") (pin "3") (pinfunction "1_3") (pintype "passive"))
    )
    (net (code "93") (name "/PRT") (class "Default")
      (node (ref "IC3") (pin "L9") (pinfunction "CRESET_B_L9") (pintype "bidirectional"))
      (node (ref "IC9") (pin "57") (pinfunction "PD10_57") (pintype "bidirectional"))
    )
    (net (code "94") (name "/QCK") (class "Default")
      (node (ref "IC9") (pin "36") (pinfunction "PB2_36") (pintype "bidirectional"))
      (node (ref "RN5") (pin "4") (pinfunction "1_4") (pintype "passive"))
    )
    (net (code "95") (name "/QCKX") (class "Default")
      (node (ref "IC3") (pin "L8") (pinfunction "IOB_103_CBSEL0_L8") (pintype "bidirectional"))
      (node (ref "RN5") (pin "8") (pinfunction "2_8") (pintype "passive"))
    )
    (net (code "96") (name "/QD0") (class "Default")
      (node (ref "IC9") (pin "58") (pinfunction "PD11_58") (pintype "bidirectional"))
      (node (ref "RN5") (pin "3") (pinfunction "1_3") (pintype "passive"))
    )
    (net (code "97") (name "/QD0X") (class "Default")
      (node (ref "IC3") (pin "H7") (pinfunction "IOB_87_H7") (pintype "bidirectional"))
      (node (ref "RN5") (pin "7") (pinfunction "2_7") (pintype "passive"))
    )
    (net (code "98") (name "/QD1") (class "Default")
      (node (ref "IC9") (pin "59") (pinfunction "PD12_59") (pintype "bidirectional"))
      (node (ref "RN5") (pin "2") (pinfunction "1_2") (pintype "passive"))
    )
    (net (code "99") (name "/QD1X") (class "Default")
      (node (ref "IC3") (pin "K7") (pinfunction "IOB_89_K7") (pintype "bidirectional"))
      (node (ref "RN4") (pin "5") (pinfunction "2_5") (pintype "passive"))
    )
    (net (code "100") (name "/QD2") (class "Default")
      (node (ref "IC9") (pin "1") (pinfunction "PE2_1") (pintype "bidirectional"))
      (node (ref "RN4") (pin "4") (pinfunction "1_4") (pintype "passive"))
    )
    (net (code "101") (name "/QD2X") (class "Default")
      (node (ref "IC3") (pin "J8") (pinfunction "IOB_91_J8") (pintype "bidirectional"))
      (node (ref "RN5") (pin "6") (pinfunction "2_6") (pintype "passive"))
    )
    (net (code "102") (name "/QD3") (class "Default")
      (node (ref "IC9") (pin "60") (pinfunction "PD13_60") (pintype "bidirectional"))
      (node (ref "RN5") (pin "1") (pinfunction "1_1") (pintype "passive"))
    )
    (net (code "103") (name "/QD3X") (class "Default")
      (node (ref "IC3") (pin "L7") (pinfunction "IOB_94_L7") (pintype "bidirectional"))
      (node (ref "RN4") (pin "6") (pinfunction "2_6") (pintype "passive"))
    )
    (net (code "104") (name "/QDR") (class "Default")
      (node (ref "IC3") (pin "J7") (pinfunction "**IOB_86_J7") (pintype "bidirectional"))
      (node (ref "IC9") (pin "62") (pinfunction "PD15_62") (pintype "bidirectional"))
    )
    (net (code "105") (name "/RX") (class "Default")
      (node (ref "IC3") (pin "J11") (pinfunction "IOR_114_J11") (pintype "bidirectional"))
      (node (ref "IC9") (pin "68") (pinfunction "PA9_68") (pintype "bidirectional"))
      (node (ref "MEZZANINE") (pin "F1") (pinfunction "F1_F1") (pintype "bidirectional"))
    )
    (net (code "106") (name "/RXA") (class "Default")
      (node (ref "IC9") (pin "87") (pinfunction "PD6_87") (pintype "bidirectional"))
      (node (ref "MEZZANINE") (pin "E16") (pinfunction "E16_E16") (pintype "bidirectional"))
    )
    (net (code "107") (name "/R{slash}~{DS}") (class "Default")
      (node (ref "IC3") (pin "B6") (pinfunction "IOT_198_GBIN0_B6") (pintype "bidirectional"))
      (node (ref "MEZZANINE") (pin "F24") (pinfunction "F24_F24") (pintype "bidirectional"))
    )
    (net (code "108") (name "/SCD") (class "Default")
      (node (ref "IC9") (pin "83") (pinfunction "PD2_83") (pintype "bidirectional"))
      (node (ref "RN101") (pin "2") (pinfunction "1_2") (pintype "passive"))
      (node (ref "SD100") (pin "P$7") (pinfunction "CMD/DI_P$7") (pintype "bidirectional"))
    )
    (net (code "109") (name "/SCK") (class "Default")
      (node (ref "IC3") (pin "L10") (pinfunction "IOB_107_SCK_L10") (pintype "bidirectional"))
      (node (ref "IC4") (pin "6") (pinfunction "SCK_6") (pintype "bidirectional"))
      (node (ref "IC9") (pin "42") (pinfunction "PE12_42") (pintype "bidirectional"))
      (node (ref "MEZZANINE") (pin "F3") (pinfunction "F3_F3") (pintype "bidirectional"))
      (node (ref "RN102") (pin "3") (pinfunction "1_3") (pintype "passive"))
    )
    (net (code "110") (name "/SCL") (class "Default")
      (node (ref "IC10") (pin "6") (pinfunction "SCL_6") (pintype "bidirectional"))
      (node (ref "IC9") (pin "46") (pinfunction "PB10_46") (pintype "bidirectional"))
      (node (ref "MEZZANINE") (pin "F20") (pinfunction "F20_F20") (pintype "bidirectional"))
      (node (ref "RN6") (pin "6") (pinfunction "2_6") (pintype "passive"))
      (node (ref "TILE3") (pin "P$39") (pinfunction "ICL_P$39") (pintype "bidirectional"))
      (node (ref "TILE5") (pin "P$39") (pinfunction "ICL_P$39") (pintype "bidirectional"))
    )
    (net (code "111") (name "/SCL2") (class "Default")
      (node (ref "IC9") (pin "95") (pinfunction "PB8_95") (pintype "bidirectional"))
      (node (ref "MEZZANINE") (pin "E10") (pinfunction "E10_E10") (pintype "bidirectional"))
      (node (ref "RN7") (pin "8") (pinfunction "2_8") (pintype "passive"))
      (node (ref "TILE1") (pin "P$39") (pinfunction "ICL_P$39") (pintype "bidirectional"))
      (node (ref "TILE4") (pin "P$39") (pinfunction "ICL_P$39") (pintype "bidirectional"))
    )
    (net (code "112") (name "/SD") (class "Default")
      (node (ref "IC9") (pin "77") (pinfunction "PA15_77") (pintype "bidirectional"))
      (node (ref "RN100") (pin "1") (pinfunction "1_1") (pintype "passive"))
      (node (ref "SD100") (pin "P$1") (pinfunction "CD_P$1") (pintype "bidirectional"))
    )
    (net (code "113") (name "/SD0") (class "Default")
      (node (ref "IC9") (pin "65") (pinfunction "PC8_65") (pintype "bidirectional"))
      (node (ref "RN100") (pin "3") (pinfunction "1_3") (pintype "passive"))
      (node (ref "SD100") (pin "P$3") (pinfunction "D0/DO_P$3") (pintype "bidirectional"))
    )
    (net (code "114") (name "/SD1") (class "Default")
      (node (ref "IC9") (pin "66") (pinfunction "PC9_66") (pintype "bidirectional"))
      (node (ref "RN100") (pin "2") (pinfunction "1_2") (pintype "passive"))
      (node (ref "SD100") (pin "P$2") (pinfunction "D1_P$2") (pintype "bidirectional"))
    )
    (net (code "115") (name "/SD2") (class "Default")
      (node (ref "IC9") (pin "78") (pinfunction "PC10_78") (pintype "bidirectional"))
      (node (ref "RN101") (pin "4") (pinfunction "1_4") (pintype "passive"))
      (node (ref "SD100") (pin "P$9") (pinfunction "D2_P$9") (pintype "bidirectional"))
    )
    (net (code "116") (name "/SD3") (class "Default")
      (node (ref "IC9") (pin "79") (pinfunction "PC11_79") (pintype "bidirectional"))
      (node (ref "RN101") (pin "3") (pinfunction "1_3") (pintype "passive"))
      (node (ref "SD100") (pin "P$8") (pinfunction "CD/D3_P$8") (pintype "bidirectional"))
    )
    (net (code "117") (name "/SDA") (class "Default")
      (node (ref "IC10") (pin "7") (pinfunction "SDA_7") (pintype "bidirectional"))
      (node (ref "IC9") (pin "47") (pinfunction "PB11_47") (pintype "bidirectional"))
      (node (ref "MEZZANINE") (pin "F5") (pinfunction "F5_F5") (pintype "bidirectional"))
      (node (ref "RN6") (pin "5") (pinfunction "2_5") (pintype "passive"))
      (node (ref "TILE3") (pin "P$14") (pinfunction "IDA_P$14") (pintype "bidirectional"))
      (node (ref "TILE5") (pin "P$14") (pinfunction "IDA_P$14") (pintype "bidirectional"))
    )
    (net (code "118") (name "/SDA2") (class "Default")
      (node (ref "IC9") (pin "96") (pinfunction "PB9_96") (pintype "bidirectional"))
      (node (ref "MEZZANINE") (pin "E15") (pinfunction "E15_E15") (pintype "bidirectional"))
      (node (ref "RN7") (pin "7") (pinfunction "2_7") (pintype "passive"))
      (node (ref "TILE1") (pin "P$14") (pinfunction "IDA_P$14") (pintype "bidirectional"))
      (node (ref "TILE4") (pin "P$14") (pinfunction "IDA_P$14") (pintype "bidirectional"))
    )
    (net (code "119") (name "/SDK") (class "Default")
      (node (ref "IC9") (pin "80") (pinfunction "PC12_80") (pintype "bidirectional"))
      (node (ref "RN101") (pin "1") (pinfunction "1_1") (pintype "passive"))
      (node (ref "SD100") (pin "P$5") (pinfunction "CLK_P$5") (pintype "bidirectional"))
    )
    (net (code "120") (name "/SHA") (class "Default")
      (node (ref "CN1") (pin "P$1") (pinfunction "SHLD_P$1") (pintype "passive"))
      (node (ref "CN1") (pin "P$2") (pinfunction "SHLD_P$2") (pintype "passive"))
      (node (ref "CN1") (pin "P$3") (pinfunction "SHLD_P$3") (pintype "passive"))
      (node (ref "CN1") (pin "P$4") (pinfunction "SHLD_P$4") (pintype "passive"))
      (node (ref "RN9") (pin "5") (pinfunction "2_5") (pintype "passive"))
    )
    (net (code "121") (name "/SHB") (class "Default")
      (node (ref "CN2") (pin "P$1") (pinfunction "SHLD_P$1") (pintype "passive"))
      (node (ref "CN2") (pin "P$2") (pinfunction "SHLD_P$2") (pintype "passive"))
      (node (ref "CN2") (pin "P$3") (pinfunction "SHLD_P$3") (pintype "passive"))
      (node (ref "CN2") (pin "P$4") (pinfunction "SHLD_P$4") (pintype "passive"))
      (node (ref "RN8") (pin "4") (pinfunction "1_4") (pintype "passive"))
    )
    (net (code "122") (name "/SI") (class "Default")
      (node (ref "IC3") (pin "K9") (pinfunction "IOB_105_SDO_K9") (pintype "bidirectional"))
      (node (ref "IC4") (pin "5") (pinfunction "SI_5") (pintype "bidirectional"))
      (node (ref "IC9") (pin "44") (pinfunction "PE14_44") (pintype "bidirectional"))
      (node (ref "MEZZANINE") (pin "F21") (pinfunction "F21_F21") (pintype "bidirectional"))
      (node (ref "RN102") (pin "1") (pinfunction "1_1") (pintype "passive"))
    )
    (net (code "123") (name "/SO") (class "Default")
      (node (ref "IC3") (pin "J9") (pinfunction "IOB_106_SDI_J9") (pintype "bidirectional"))
      (node (ref "IC4") (pin "2") (pinfunction "SO_2") (pintype "bidirectional"))
      (node (ref "IC9") (pin "43") (pinfunction "PE13_43") (pintype "bidirectional"))
      (node (ref "MEZZANINE") (pin "F4") (pinfunction "F4_F4") (pintype "bidirectional"))
      (node (ref "RN102") (pin "2") (pinfunction "1_2") (pintype "passive"))
    )
    (net (code "124") (name "/SWCLK") (class "Default")
      (node (ref "CN3") (pin "2") (pinfunction "2_2") (pintype "bidirectional"))
      (node (ref "IC9") (pin "76") (pinfunction "PA14_76") (pintype "bidirectional"))
    )
    (net (code "125") (name "/SWDIO") (class "Default")
      (node (ref "CN3") (pin "1") (pinfunction "1_1") (pintype "bidirectional"))
      (node (ref "IC9") (pin "72") (pinfunction "PA13_72") (pintype "bidirectional"))
    )
    (net (code "126") (name "/SWO") (class "Default")
      (node (ref "CN3") (pin "3") (pinfunction "3_3") (pintype "bidirectional"))
      (node (ref "IC9") (pin "89") (pinfunction "PB3_89") (pintype "bidirectional"))
    )
    (net (code "127") (name "/TB0") (class "Default")
      (node (ref "IC3") (pin "B1") (pinfunction "IOL_2A_B1") (pintype "bidirectional"))
      (node (ref "TILE1") (pin "P$8") (pinfunction "D0_P$8") (pintype "bidirectional"))
    )
    (net (code "128") (name "/TB1") (class "Default")
      (node (ref "IC3") (pin "B2") (pinfunction "IOL_2B_B2") (pintype "bidirectional"))
      (node (ref "TILE1") (pin "P$33") (pinfunction "D1_P$33") (pintype "bidirectional"))
    )
    (net (code "129") (name "/TB2") (class "Default")
      (node (ref "IC3") (pin "C4") (pinfunction "IOL_4A_C4") (pintype "bidirectional"))
      (node (ref "TILE1") (pin "P$9") (pinfunction "D2_P$9") (pintype "bidirectional"))
    )
    (net (code "130") (name "/TB3") (class "Default")
      (node (ref "IC3") (pin "C3") (pinfunction "IOL_4B_C3") (pintype "bidirectional"))
      (node (ref "TILE1") (pin "P$34") (pinfunction "D3_P$34") (pintype "bidirectional"))
    )
    (net (code "131") (name "/TB4") (class "Default")
      (node (ref "IC3") (pin "C2") (pinfunction "IOL_5A_C2") (pintype "bidirectional"))
      (node (ref "TILE1") (pin "P$10") (pinfunction "D4_P$10") (pintype "bidirectional"))
    )
    (net (code "132") (name "/TB5") (class "Default")
      (node (ref "IC3") (pin "C1") (pinfunction "IOL_5B_C1") (pintype "bidirectional"))
      (node (ref "TILE1") (pin "P$35") (pinfunction "D5_P$35") (pintype "bidirectional"))
    )
    (net (code "133") (name "/TB6") (class "Default")
      (node (ref "IC3") (pin "E1") (pinfunction "IOL_8A_E1") (pintype "bidirectional"))
      (node (ref "TILE1") (pin "P$11") (pinfunction "D6_P$11") (pintype "bidirectional"))
    )
    (net (code "134") (name "/TB7") (class "Default")
      (node (ref "IC3") (pin "D1") (pinfunction "IOL_8B_D1") (pintype "bidirectional"))
      (node (ref "TILE1") (pin "P$36") (pinfunction "D7_P$36") (pintype "bidirectional"))
    )
    (net (code "135") (name "/TB8") (class "Default")
      (node (ref "IC3") (pin "D2") (pinfunction "IOL_9A_D2") (pintype "bidirectional"))
      (node (ref "TILE1") (pin "P$12") (pinfunction "D8_P$12") (pintype "bidirectional"))
    )
    (net (code "136") (name "/TB9") (class "Default")
      (node (ref "IC3") (pin "D3") (pinfunction "IOL_9B_D3") (pintype "bidirectional"))
      (node (ref "TILE1") (pin "P$37") (pinfunction "D9_P$37") (pintype "bidirectional"))
    )
    (net (code "137") (name "/TB10") (class "Default")
      (node (ref "IC3") (pin "E2") (pinfunction "IOL_10A_E2") (pintype "bidirectional"))
      (node (ref "TILE1") (pin "P$13") (pinfunction "D10_P$13") (pintype "bidirectional"))
    )
    (net (code "138") (name "/TB11") (class "Default")
      (node (ref "IC3") (pin "E3") (pinfunction "IOL_10B_E3") (pintype "bidirectional"))
      (node (ref "TILE1") (pin "P$38") (pinfunction "D12_P$38") (pintype "bidirectional"))
    )
    (net (code "139") (name "/TC0") (class "Default")
      (node (ref "IC3") (pin "F1") (pinfunction "IOL_12A_F1") (pintype "bidirectional"))
      (node (ref "TILE4") (pin "P$8") (pinfunction "D0_P$8") (pintype "bidirectional"))
    )
    (net (code "140") (name "/TC1") (class "Default")
      (node (ref "IC3") (pin "F2") (pinfunction "IOL_12B_F2") (pintype "bidirectional"))
      (node (ref "TILE4") (pin "P$33") (pinfunction "D1_P$33") (pintype "bidirectional"))
    )
    (net (code "141") (name "/TC2") (class "Default")
      (node (ref "IC3") (pin "F4") (pinfunction "IOL_13A_F4") (pintype "bidirectional"))
      (node (ref "TILE4") (pin "P$9") (pinfunction "D2_P$9") (pintype "bidirectional"))
    )
    (net (code "142") (name "/TC3") (class "Default")
      (node (ref "IC3") (pin "F3") (pinfunction "IOL_13B_GBIN7_F3") (pintype "bidirectional"))
      (node (ref "TILE4") (pin "P$34") (pinfunction "D3_P$34") (pintype "bidirectional"))
    )
    (net (code "143") (name "/TC4") (class "Default")
      (node (ref "IC3") (pin "G1") (pinfunction "IOL_14A_GBIN6_G1") (pintype "bidirectional"))
      (node (ref "TILE4") (pin "P$10") (pinfunction "D4_P$10") (pintype "bidirectional"))
    )
    (net (code "144") (name "/TC5") (class "Default")
      (node (ref "IC3") (pin "G2") (pinfunction "IOL_14B_G2") (pintype "bidirectional"))
      (node (ref "TILE4") (pin "P$35") (pinfunction "D5_P$35") (pintype "bidirectional"))
    )
    (net (code "145") (name "/TC6") (class "Default")
      (node (ref "IC3") (pin "G3") (pinfunction "IOL_17A_G3") (pintype "bidirectional"))
      (node (ref "TILE4") (pin "P$11") (pinfunction "D6_P$11") (pintype "bidirectional"))
    )
    (net (code "146") (name "/TC7") (class "Default")
      (node (ref "IC3") (pin "H3") (pinfunction "IOL_17B_H3") (pintype "bidirectional"))
      (node (ref "TILE4") (pin "P$36") (pinfunction "D7_P$36") (pintype "bidirectional"))
    )
    (net (code "147") (name "/TC8") (class "Default")
      (node (ref "IC3") (pin "H1") (pinfunction "IOL_18A_H1") (pintype "bidirectional"))
      (node (ref "TILE4") (pin "P$12") (pinfunction "D8_P$12") (pintype "bidirectional"))
    )
    (net (code "148") (name "/TC9") (class "Default")
      (node (ref "IC3") (pin "H2") (pinfunction "IOL_18B_H2") (pintype "bidirectional"))
      (node (ref "TILE4") (pin "P$37") (pinfunction "D9_P$37") (pintype "bidirectional"))
    )
    (net (code "149") (name "/TC10") (class "Default")
      (node (ref "IC3") (pin "J1") (pinfunction "IOL_23A_J1") (pintype "bidirectional"))
      (node (ref "TILE4") (pin "P$13") (pinfunction "D10_P$13") (pintype "bidirectional"))
    )
    (net (code "150") (name "/TC11") (class "Default")
      (node (ref "IC3") (pin "K1") (pinfunction "IOL_23B_K1") (pintype "bidirectional"))
      (node (ref "TILE4") (pin "P$38") (pinfunction "D12_P$38") (pintype "bidirectional"))
    )
    (net (code "151") (name "/TF0") (class "Default")
      (node (ref "IC3") (pin "A9") (pinfunction "IOT_178A_A9") (pintype "bidirectional"))
      (node (ref "TILE3") (pin "P$8") (pinfunction "D0_P$8") (pintype "bidirectional"))
    )
    (net (code "152") (name "/TF1") (class "Default")
      (node (ref "IC3") (pin "C8") (pinfunction "IOT_179B_C8") (pintype "bidirectional"))
      (node (ref "TILE3") (pin "P$33") (pinfunction "D1_P$33") (pintype "bidirectional"))
    )
    (net (code "153") (name "/TF2") (class "Default")
      (node (ref "IC3") (pin "A8") (pinfunction "IOT_190A_A8") (pintype "bidirectional"))
      (node (ref "TILE3") (pin "P$9") (pinfunction "D2_P$9") (pintype "bidirectional"))
    )
    (net (code "154") (name "/TF3") (class "Default")
      (node (ref "IC3") (pin "C7") (pinfunction "IOT_191B_C7") (pintype "bidirectional"))
      (node (ref "TILE3") (pin "P$34") (pinfunction "D3_P$34") (pintype "bidirectional"))
    )
    (net (code "155") (name "/TF4") (class "Default")
      (node (ref "IC3") (pin "A6") (pinfunction "IOT_206A_A6") (pintype "bidirectional"))
      (node (ref "TILE3") (pin "P$10") (pinfunction "D4_P$10") (pintype "bidirectional"))
    )
    (net (code "156") (name "/TF5") (class "Default")
      (node (ref "IC3") (pin "A5") (pinfunction "IOT_207B_A5") (pintype "bidirectional"))
      (node (ref "TILE3") (pin "P$35") (pinfunction "D5_P$35") (pintype "bidirectional"))
    )
    (net (code "157") (name "/TF6") (class "Default")
      (node (ref "IC3") (pin "A2") (pinfunction "IOT_222A_A2") (pintype "bidirectional"))
      (node (ref "TILE3") (pin "P$11") (pinfunction "D6_P$11") (pintype "bidirectional"))
    )
    (net (code "158") (name "/TF7") (class "Default")
      (node (ref "IC3") (pin "A3") (pinfunction "IOT_223B_A3") (pintype "bidirectional"))
      (node (ref "TILE3") (pin "P$36") (pinfunction "D7_P$36") (pintype "bidirectional"))
    )
    (net (code "159") (name "/TF8") (class "Default")
      (node (ref "IC3") (pin "F11") (pinfunction "IOR_140_GBIN3_F11") (pintype "bidirectional"))
      (node (ref "TILE3") (pin "P$12") (pinfunction "D8_P$12") (pintype "bidirectional"))
    )
    (net (code "160") (name "/TF9") (class "Default")
      (node (ref "IC3") (pin "E9") (pinfunction "IOR_144_E9") (pintype "bidirectional"))
      (node (ref "TILE3") (pin "P$37") (pinfunction "D9_P$37") (pintype "bidirectional"))
    )
    (net (code "161") (name "/TF10") (class "Default")
      (node (ref "IC3") (pin "E10") (pinfunction "IOR_141_GBIN2_E10") (pintype "bidirectional"))
      (node (ref "TILE3") (pin "P$13") (pinfunction "D10_P$13") (pintype "bidirectional"))
    )
    (net (code "162") (name "/TF11") (class "Default")
      (node (ref "IC3") (pin "E8") (pinfunction "IOR_146_E8") (pintype "bidirectional"))
      (node (ref "TILE3") (pin "P$38") (pinfunction "D12_P$38") (pintype "bidirectional"))
    )
    (net (code "163") (name "/TG0") (class "Default")
      (node (ref "IC3") (pin "K11") (pinfunction "IOR_115A_K11") (pintype "bidirectional"))
      (node (ref "TILE5") (pin "P$8") (pinfunction "D0_P$8") (pintype "bidirectional"))
    )
    (net (code "164") (name "/TG1") (class "Default")
      (node (ref "IC3") (pin "H10") (pinfunction "IOR_116B_H10") (pintype "bidirectional"))
      (node (ref "TILE5") (pin "P$33") (pinfunction "D1_P$33") (pintype "bidirectional"))
    )
    (net (code "165") (name "/TG2") (class "Default")
      (node (ref "IC3") (pin "J10") (pinfunction "IOR_117A_J10") (pintype "bidirectional"))
      (node (ref "TILE5") (pin "P$9") (pinfunction "D2_P$9") (pintype "bidirectional"))
    )
    (net (code "166") (name "/TG3") (class "Default")
      (node (ref "IC3") (pin "G8") (pinfunction "IOR_118B_G8") (pintype "bidirectional"))
      (node (ref "TILE5") (pin "P$34") (pinfunction "D3_P$34") (pintype "bidirectional"))
    )
    (net (code "167") (name "/TG4") (class "Default")
      (node (ref "IC3") (pin "H11") (pinfunction "IOR_119A_H11") (pintype "bidirectional"))
      (node (ref "TILE5") (pin "P$10") (pinfunction "D4_P$10") (pintype "bidirectional"))
    )
    (net (code "168") (name "/TG5") (class "Default")
      (node (ref "IC3") (pin "G10") (pinfunction "IOR_120B_G10") (pintype "bidirectional"))
      (node (ref "TILE5") (pin "P$35") (pinfunction "D5_P$35") (pintype "bidirectional"))
    )
    (net (code "169") (name "/TG6") (class "Default")
      (node (ref "IC3") (pin "D9") (pinfunction "IOR_147A_D9") (pintype "bidirectional"))
      (node (ref "TILE5") (pin "P$11") (pinfunction "D6_P$11") (pintype "bidirectional"))
    )
    (net (code "170") (name "/TG7") (class "Default")
      (node (ref "IC3") (pin "E11") (pinfunction "IOR_148B_E11") (pintype "bidirectional"))
      (node (ref "TILE5") (pin "P$36") (pinfunction "D7_P$36") (pintype "bidirectional"))
    )
    (net (code "171") (name "/TG8") (class "Default")
      (node (ref "IC3") (pin "G9") (pinfunction "IOR_128_G9") (pintype "bidirectional"))
      (node (ref "TILE5") (pin "P$12") (pinfunction "D8_P$12") (pintype "bidirectional"))
    )
    (net (code "172") (name "/TG9") (class "Default")
      (node (ref "IC3") (pin "G11") (pinfunction "IOR_129_G11") (pintype "bidirectional"))
      (node (ref "TILE5") (pin "P$37") (pinfunction "D9_P$37") (pintype "bidirectional"))
    )
    (net (code "173") (name "/TG10") (class "Default")
      (node (ref "IC3") (pin "F10") (pinfunction "IOR_136_F10") (pintype "bidirectional"))
      (node (ref "TILE5") (pin "P$13") (pinfunction "D10_P$13") (pintype "bidirectional"))
    )
    (net (code "174") (name "/TG11") (class "Default")
      (node (ref "IC3") (pin "F9") (pinfunction "IOR_137_F9") (pintype "bidirectional"))
      (node (ref "TILE5") (pin "P$38") (pinfunction "D12_P$38") (pintype "bidirectional"))
    )
    (net (code "175") (name "/TR1") (class "Default")
      (node (ref "IC9") (pin "52") (pinfunction "PB13_52") (pintype "bidirectional"))
      (node (ref "TILE3") (pin "P$41") (pinfunction "TR_P$41") (pintype "bidirectional"))
    )
    (net (code "176") (name "/TR2") (class "Default")
      (node (ref "IC9") (pin "51") (pinfunction "PB12_51") (pintype "bidirectional"))
      (node (ref "TILE5") (pin "P$41") (pinfunction "TR_P$41") (pintype "bidirectional"))
    )
    (net (code "177") (name "/TR3") (class "Default")
      (node (ref "IC9") (pin "2") (pinfunction "PE3_2") (pintype "bidirectional"))
      (node (ref "TILE4") (pin "P$41") (pinfunction "TR_P$41") (pintype "bidirectional"))
    )
    (net (code "178") (name "/TR4") (class "Default")
      (node (ref "IC9") (pin "7") (pinfunction "PC13-ANTI_TAMP_7") (pintype "bidirectional"))
      (node (ref "TILE1") (pin "P$41") (pinfunction "TR_P$41") (pintype "bidirectional"))
    )
    (net (code "179") (name "/TR5") (class "Default")
      (node (ref "IC9") (pin "55") (pinfunction "PD8_55") (pintype "bidirectional"))
    )
    (net (code "180") (name "/TR6") (class "Default")
      (node (ref "IC9") (pin "56") (pinfunction "PD9_56") (pintype "bidirectional"))
    )
    (net (code "181") (name "/TX") (class "Default")
      (node (ref "IC3") (pin "D7") (pinfunction "IOT_181_D7") (pintype "bidirectional"))
      (node (ref "IC9") (pin "69") (pinfunction "PA10_69") (pintype "bidirectional"))
      (node (ref "MEZZANINE") (pin "F2") (pinfunction "F2_F2") (pintype "bidirectional"))
      (node (ref "RN8") (pin "6") (pinfunction "2_6") (pintype "passive"))
    )
    (net (code "182") (name "/TXA") (class "Default")
      (node (ref "IC9") (pin "86") (pinfunction "PD5_86") (pintype "bidirectional"))
      (node (ref "MEZZANINE") (pin "E9") (pinfunction "E9_E9") (pintype "bidirectional"))
    )
    (net (code "183") (name "/VB+") (class "Default")
      (node (ref "C19") (pin "1") (pinfunction "1_1") (pintype "passive"))
      (node (ref "D2") (pin "C") (pinfunction "C_C") (pintype "passive"))
      (node (ref "H4") (pin "P$1") (pinfunction "P_P$1") (pintype "bidirectional"))
      (node (ref "MEZZANINE") (pin "F13") (pinfunction "F13_F13") (pintype "bidirectional"))
      (node (ref "MEZZANINE") (pin "F14") (pinfunction "F14_F14") (pintype "bidirectional"))
      (node (ref "MEZZANINE") (pin "F15") (pinfunction "F15_F15") (pintype "bidirectional"))
      (node (ref "MEZZANINE") (pin "F16") (pinfunction "F16_F16") (pintype "bidirectional"))
      (node (ref "MEZZANINE") (pin "F17") (pinfunction "F17_F17") (pintype "bidirectional"))
      (node (ref "MEZZANINE") (pin "F18") (pinfunction "F18_F18") (pintype "bidirectional"))
      (node (ref "TILE1") (pin "P$20") (pinfunction "V+_P$20") (pintype "power_in"))
      (node (ref "TILE1") (pin "P$21") (pinfunction "V+_P$21") (pintype "power_in"))
      (node (ref "TILE1") (pin "P$22") (pinfunction "V+_P$22") (pintype "power_in"))
      (node (ref "TILE1") (pin "P$23") (pinfunction "V+_P$23") (pintype "power_in"))
      (node (ref "TILE1") (pin "P$24") (pinfunction "V+_P$24") (pintype "power_in"))
      (node (ref "TILE1") (pin "P$25") (pinfunction "V+_P$25") (pintype "power_in"))
      (node (ref "TILE1") (pin "P$45") (pinfunction "V+_P$45") (pintype "power_in"))
      (node (ref "TILE1") (pin "P$46") (pinfunction "V+_P$46") (pintype "power_in"))
      (node (ref "TILE1") (pin "P$47") (pinfunction "V+_P$47") (pintype "power_in"))
      (node (ref "TILE1") (pin "P$48") (pinfunction "V+_P$48") (pintype "power_in"))
      (node (ref "TILE1") (pin "P$49") (pinfunction "V+_P$49") (pintype "power_in"))
      (node (ref "TILE1") (pin "P$50") (pinfunction "V+_P$50") (pintype "power_in"))
      (node (ref "TILE2") (pin "P$20") (pinfunction "V+_P$20") (pintype "power_in"))
      (node (ref "TILE2") (pin "P$21") (pinfunction "V+_P$21") (pintype "power_in"))
      (node (ref "TILE2") (pin "P$22") (pinfunction "V+_P$22") (pintype "power_in"))
      (node (ref "TILE2") (pin "P$23") (pinfunction "V+_P$23") (pintype "power_in"))
      (node (ref "TILE2") (pin "P$24") (pinfunction "V+_P$24") (pintype "power_in"))
      (node (ref "TILE2") (pin "P$25") (pinfunction "V+_P$25") (pintype "power_in"))
      (node (ref "TILE2") (pin "P$45") (pinfunction "V+_P$45") (pintype "power_in"))
      (node (ref "TILE2") (pin "P$46") (pinfunction "V+_P$46") (pintype "power_in"))
      (node (ref "TILE2") (pin "P$47") (pinfunction "V+_P$47") (pintype "power_in"))
      (node (ref "TILE2") (pin "P$48") (pinfunction "V+_P$48") (pintype "power_in"))
      (node (ref "TILE2") (pin "P$49") (pinfunction "V+_P$49") (pintype "power_in"))
      (node (ref "TILE2") (pin "P$50") (pinfunction "V+_P$50") (pintype "power_in"))
      (node (ref "TILE3") (pin "P$20") (pinfunction "V+_P$20") (pintype "power_in"))
      (node (ref "TILE3") (pin "P$21") (pinfunction "V+_P$21") (pintype "power_in"))
      (node (ref "TILE3") (pin "P$22") (pinfunction "V+_P$22") (pintype "power_in"))
      (node (ref "TILE3") (pin "P$23") (pinfunction "V+_P$23") (pintype "power_in"))
      (node (ref "TILE3") (pin "P$24") (pinfunction "V+_P$24") (pintype "power_in"))
      (node (ref "TILE3") (pin "P$25") (pinfunction "V+_P$25") (pintype "power_in"))
      (node (ref "TILE3") (pin "P$45") (pinfunction "V+_P$45") (pintype "power_in"))
      (node (ref "TILE3") (pin "P$46") (pinfunction "V+_P$46") (pintype "power_in"))
      (node (ref "TILE3") (pin "P$47") (pinfunction "V+_P$47") (pintype "power_in"))
      (node (ref "TILE3") (pin "P$48") (pinfunction "V+_P$48") (pintype "power_in"))
      (node (ref "TILE3") (pin "P$49") (pinfunction "V+_P$49") (pintype "power_in"))
      (node (ref "TILE3") (pin "P$50") (pinfunction "V+_P$50") (pintype "power_in"))
      (node (ref "TILE4") (pin "P$20") (pinfunction "V+_P$20") (pintype "power_in"))
      (node (ref "TILE4") (pin "P$21") (pinfunction "V+_P$21") (pintype "power_in"))
      (node (ref "TILE4") (pin "P$22") (pinfunction "V+_P$22") (pintype "power_in"))
      (node (ref "TILE4") (pin "P$23") (pinfunction "V+_P$23") (pintype "power_in"))
      (node (ref "TILE4") (pin "P$24") (pinfunction "V+_P$24") (pintype "power_in"))
      (node (ref "TILE4") (pin "P$25") (pinfunction "V+_P$25") (pintype "power_in"))
      (node (ref "TILE4") (pin "P$45") (pinfunction "V+_P$45") (pintype "power_in"))
      (node (ref "TILE4") (pin "P$46") (pinfunction "V+_P$46") (pintype "power_in"))
      (node (ref "TILE4") (pin "P$47") (pinfunction "V+_P$47") (pintype "power_in"))
      (node (ref "TILE4") (pin "P$48") (pinfunction "V+_P$48") (pintype "power_in"))
      (node (ref "TILE4") (pin "P$49") (pinfunction "V+_P$49") (pintype "power_in"))
      (node (ref "TILE4") (pin "P$50") (pinfunction "V+_P$50") (pintype "power_in"))
      (node (ref "TILE5") (pin "P$20") (pinfunction "V+_P$20") (pintype "power_in"))
      (node (ref "TILE5") (pin "P$21") (pinfunction "V+_P$21") (pintype "power_in"))
      (node (ref "TILE5") (pin "P$22") (pinfunction "V+_P$22") (pintype "power_in"))
      (node (ref "TILE5") (pin "P$23") (pinfunction "V+_P$23") (pintype "power_in"))
      (node (ref "TILE5") (pin "P$24") (pinfunction "V+_P$24") (pintype "power_in"))
      (node (ref "TILE5") (pin "P$25") (pinfunction "V+_P$25") (pintype "power_in"))
      (node (ref "TILE5") (pin "P$45") (pinfunction "V+_P$45") (pintype "power_in"))
      (node (ref "TILE5") (pin "P$46") (pinfunction "V+_P$46") (pintype "power_in"))
      (node (ref "TILE5") (pin "P$47") (pinfunction "V+_P$47") (pintype "power_in"))
      (node (ref "TILE5") (pin "P$48") (pinfunction "V+_P$48") (pintype "power_in"))
      (node (ref "TILE5") (pin "P$49") (pinfunction "V+_P$49") (pintype "power_in"))
      (node (ref "TILE5") (pin "P$50") (pinfunction "V+_P$50") (pintype "power_in"))
    )
    (net (code "184") (name "/VBAT") (class "Default")
      (node (ref "BT100") (pin "1") (pinfunction "+_1") (pintype "power_in"))
      (node (ref "C23") (pin "1") (pinfunction "1_1") (pintype "passive"))
      (node (ref "IC9") (pin "6") (pinfunction "VBAT_6") (pintype "bidirectional"))
    )
    (net (code "185") (name "/VBUSA") (class "Default")
      (node (ref "CN1") (pin "VBUS@1") (pinfunction "VBUS_VBUS@1") (pintype "power_in"))
      (node (ref "CN1") (pin "VBUS@2") (pinfunction "VBUS_VBUS@2") (pintype "power_in"))
      (node (ref "D1") (pin "A") (pinfunction "A_A") (pintype "passive"))
      (node (ref "IC8") (pin "5") (pinfunction "VBUS_5") (pintype "bidirectional"))
    )
    (net (code "186") (name "/VBUSB") (class "Default")
      (node (ref "CN2") (pin "VBUS@1") (pinfunction "VBUS_VBUS@1") (pintype "power_in"))
      (node (ref "CN2") (pin "VBUS@2") (pinfunction "VBUS_VBUS@2") (pintype "power_in"))
      (node (ref "D2") (pin "A") (pinfunction "A_A") (pintype "passive"))
      (node (ref "IC10") (pin "2") (pinfunction "VBUS_2") (pintype "bidirectional"))
    )
    (net (code "187") (name "/VCC") (class "Default")
      (node (ref "C107") (pin "2") (pinfunction "2_2") (pintype "passive"))
      (node (ref "C109") (pin "2") (pinfunction "2_2") (pintype "passive"))
      (node (ref "C110") (pin "2") (pinfunction "2_2") (pintype "passive"))
      (node (ref "C4") (pin "1") (pinfunction "1_1") (pintype "passive"))
      (node (ref "C5") (pin "2") (pinfunction "2_2") (pintype "passive"))
      (node (ref "I1") (pin "P$2") (pinfunction "P$2_P$2") (pintype "passive"))
      (node (ref "IC3") (pin "D4") (pinfunction "VCC_1_D4") (pintype "bidirectional"))
      (node (ref "IC3") (pin "D8") (pinfunction "VCC_2_D8") (pintype "bidirectional"))
      (node (ref "IC3") (pin "H4") (pinfunction "VCC_3_H4") (pintype "bidirectional"))
      (node (ref "IC3") (pin "H8") (pinfunction "VCC_4_H8") (pintype "bidirectional"))
      (node (ref "R3") (pin "1") (pinfunction "1_1") (pintype "passive"))
      (node (ref "R4") (pin "2") (pinfunction "2_2") (pintype "passive"))
      (node (ref "RN10") (pin "8") (pinfunction "2_8") (pintype "passive"))
    )
    (net (code "188") (name "/VPLL0") (class "Default")
      (node (ref "C104") (pin "2") (pinfunction "2_2") (pintype "passive"))
      (node (ref "C105") (pin "2") (pinfunction "2_2") (pintype "passive"))
      (node (ref "IC3") (pin "J6") (pinfunction "VCCPLL0_J6") (pintype "bidirectional"))
      (node (ref "R4") (pin "1") (pinfunction "1_1") (pintype "passive"))
    )
    (net (code "189") (name "/VPLL1") (class "Default")
      (node (ref "C111") (pin "2") (pinfunction "2_2") (pintype "passive"))
      (node (ref "C113") (pin "2") (pinfunction "2_2") (pintype "passive"))
      (node (ref "IC3") (pin "C6") (pinfunction "VCCPLL1_C6") (pintype "bidirectional"))
      (node (ref "R3") (pin "2") (pinfunction "2_2") (pintype "passive"))
    )
    (net (code "190") (name "/WP") (class "Default")
      (node (ref "IC4") (pin "3") (pinfunction "WP_3") (pintype "bidirectional"))
      (node (ref "IC9") (pin "40") (pinfunction "PE10_40") (pintype "bidirectional"))
    )
    (net (code "191") (name "/~{HRST}") (class "Default")
      (node (ref "IC9") (pin "81") (pinfunction "PD0_81") (pintype "bidirectional"))
    )
    (net (code "192") (name "/~{QSSX}") (class "Default")
      (node (ref "IC3") (pin "H9") (pinfunction "IOB_104_CBSEL1_H9") (pintype "bidirectional"))
      (node (ref "RN5") (pin "5") (pinfunction "2_5") (pintype "passive"))
    )
    (net (code "193") (name "/~{QSS}") (class "Default")
      (node (ref "IC9") (pin "92") (pinfunction "PB6_92") (pintype "bidirectional"))
      (node (ref "RN4") (pin "3") (pinfunction "1_3") (pintype "passive"))
    )
    (net (code "194") (name "/~{SRST}") (class "Default")
      (node (ref "C24") (pin "2") (pinfunction "2_2") (pintype "passive"))
      (node (ref "CN3") (pin "5") (pinfunction "5_5") (pintype "bidirectional"))
      (node (ref "IC9") (pin "14") (pinfunction "NRST_14") (pintype "bidirectional"))
      (node (ref "RN100") (pin "4") (pinfunction "1_4") (pintype "passive"))
    )
    (net (code "195") (name "/~{SS}") (class "Default")
      (node (ref "IC3") (pin "K10") (pinfunction "IOB_108_SS_K10") (pintype "bidirectional"))
      (node (ref "IC4") (pin "1") (pinfunction "CS_1") (pintype "input"))
      (node (ref "IC9") (pin "41") (pinfunction "PE11_41") (pintype "bidirectional"))
      (node (ref "RN102") (pin "4") (pinfunction "1_4") (pintype "passive"))
    )
    (net (code "196") (name "/~{TRSTA}") (class "Default")
      (node (ref "IC9") (pin "97") (pinfunction "PE0_97") (pintype "bidirectional"))
      (node (ref "TILE1") (pin "P$15") (pinfunction "PRG/RS_P$15") (pintype "open_collector"))
      (node (ref "TILE2") (pin "P$15") (pinfunction "PRG/RS_P$15") (pintype "open_collector"))
      (node (ref "TILE4") (pin "P$15") (pinfunction "PRG/RS_P$15") (pintype "open_collector"))
    )
    (net (code "197") (name "/~{TRSTB}") (class "Default")
      (node (ref "IC9") (pin "37") (pinfunction "PE7_37") (pintype "bidirectional"))
      (node (ref "TILE3") (pin "P$15") (pinfunction "PRG/RS_P$15") (pintype "open_collector"))
      (node (ref "TILE5") (pin "P$15") (pinfunction "PRG/RS_P$15") (pintype "open_collector"))
    )
    (net (code "198") (name "GND") (class "Default")
      (node (ref "BT100") (pin "2") (pinfunction "-_2") (pintype "power_in"))
      (node (ref "C1") (pin "1") (pinfunction "1_1") (pintype "passive"))
      (node (ref "C10") (pin "2") (pinfunction "2_2") (pintype "passive"))
      (node (ref "C100") (pin "2") (pinfunction "2_2") (pintype "passive"))
      (node (ref "C101") (pin "1") (pinfunction "1_1") (pintype "passive"))
      (node (ref "C106") (pin "2") (pinfunction "2_2") (pintype "passive"))
      (node (ref "C107") (pin "1") (pinfunction "1_1") (pintype "passive"))
      (node (ref "C108") (pin "2") (pinfunction "2_2") (pintype "passive"))
      (node (ref "C109") (pin "1") (pinfunction "1_1") (pintype "passive"))
      (node (ref "C110") (pin "1") (pinfunction "1_1") (pintype "passive"))
      (node (ref "C112") (pin "2") (pinfunction "2_2") (pintype "passive"))
      (node (ref "C12") (pin "2") (pinfunction "2_2") (pintype "passive"))
      (node (ref "C13") (pin "2") (pinfunction "2_2") (pintype "passive"))
      (node (ref "C14") (pin "1") (pinfunction "1_1") (pintype "passive"))
      (node (ref "C15") (pin "2") (pinfunction "2_2") (pintype "passive"))
      (node (ref "C16") (pin "1") (pinfunction "1_1") (pintype "passive"))
      (node (ref "C17") (pin "1") (pinfunction "1_1") (pintype "passive"))
      (node (ref "C18") (pin "1") (pinfunction "1_1") (pintype "passive"))
      (node (ref "C19") (pin "2") (pinfunction "2_2") (pintype "passive"))
      (node (ref "C2") (pin "2") (pinfunction "2_2") (pintype "passive"))
      (node (ref "C20") (pin "2") (pinfunction "2_2") (pintype "passive"))
      (node (ref "C21") (pin "1") (pinfunction "1_1") (pintype "passive"))
      (node (ref "C22") (pin "1") (pinfunction "1_1") (pintype "passive"))
      (node (ref "C23") (pin "2") (pinfunction "2_2") (pintype "passive"))
      (node (ref "C24") (pin "1") (pinfunction "1_1") (pintype "passive"))
      (node (ref "C25") (pin "2") (pinfunction "2_2") (pintype "passive"))
      (node (ref "C26") (pin "1") (pinfunction "1_1") (pintype "passive"))
      (node (ref "C27") (pin "1") (pinfunction "1_1") (pintype "passive"))
      (node (ref "C28") (pin "1") (pinfunction "1_1") (pintype "passive"))
      (node (ref "C29") (pin "1") (pinfunction "1_1") (pintype "passive"))
      (node (ref "C3") (pin "1") (pinfunction "1_1") (pintype "passive"))
      (node (ref "C31") (pin "1") (pinfunction "1_1") (pintype "passive"))
      (node (ref "C32") (pin "1") (pinfunction "1_1") (pintype "passive"))
      (node (ref "C33") (pin "2") (pinfunction "2_2") (pintype "passive"))
      (node (ref "C34") (pin "1") (pinfunction "1_1") (pintype "passive"))
      (node (ref "C4") (pin "2") (pinfunction "2_2") (pintype "passive"))
      (node (ref "C6") (pin "1") (pinfunction "1_1") (pintype "passive"))
      (node (ref "C7") (pin "1") (pinfunction "1_1") (pintype "passive"))
      (node (ref "C8") (pin "1") (pinfunction "1_1") (pintype "passive"))
      (node (ref "C9") (pin "2") (pinfunction "2_2") (pintype "passive"))
      (node (ref "CN1") (pin "GND@1") (pinfunction "GND_GND@1") (pintype "power_in"))
      (node (ref "CN1") (pin "GND@2") (pinfunction "GND_GND@2") (pintype "power_in"))
      (node (ref "CN2") (pin "GND@1") (pinfunction "GND_GND@1") (pintype "power_in"))
      (node (ref "CN2") (pin "GND@2") (pinfunction "GND_GND@2") (pintype "power_in"))
      (node (ref "CN3") (pin "6") (pinfunction "6_6") (pintype "bidirectional"))
      (node (ref "CN3") (pin "8") (pinfunction "8_8") (pintype "bidirectional"))
      (node (ref "CN3") (pin "9") (pinfunction "9_9") (pintype "bidirectional"))
      (node (ref "H3") (pin "P$1") (pinfunction "P_P$1") (pintype "bidirectional"))
      (node (ref "IC1") (pin "2") (pinfunction "GND_2") (pintype "power_in"))
      (node (ref "IC10") (pin "8") (pinfunction "GND_1_8") (pintype "bidirectional"))
      (node (ref "IC10") (pin "9") (pinfunction "GND_2_9") (pintype "bidirectional"))
      (node (ref "IC2") (pin "2") (pinfunction "GND_2") (pintype "power_in"))
      (node (ref "IC3") (pin "E5") (pinfunction "GND_1_E5") (pintype "bidirectional"))
      (node (ref "IC3") (pin "E6") (pinfunction "GND_2_E6") (pintype "bidirectional"))
      (node (ref "IC3") (pin "E7") (pinfunction "GND_3_E7") (pintype "bidirectional"))
      (node (ref "IC3") (pin "F5") (pinfunction "GND_4_F5") (pintype "bidirectional"))
      (node (ref "IC3") (pin "F6") (pinfunction "GND_5_F6") (pintype "bidirectional"))
      (node (ref "IC3") (pin "F7") (pinfunction "GND_6_F7") (pintype "bidirectional"))
      (node (ref "IC3") (pin "G5") (pinfunction "GND_7_G5") (pintype "bidirectional"))
      (node (ref "IC3") (pin "G6") (pinfunction "GND_8_G6") (pintype "bidirectional"))
      (node (ref "IC3") (pin "G7") (pinfunction "GND_9_G7") (pintype "bidirectional"))
      (node (ref "IC3") (pin "H5") (pinfunction "GND_10_H5") (pintype "bidirectional"))
      (node (ref "IC4") (pin "4") (pinfunction "GND_4") (pintype "power_in"))
      (node (ref "IC5") (pin "2") (pinfunction "GND_2") (pintype "power_in"))
      (node (ref "IC7") (pin "2") (pinfunction "GND_2") (pintype "bidirectional"))
      (node (ref "IC8") (pin "2") (pinfunction "GND_2") (pintype "bidirectional"))
      (node (ref "IC9") (pin "19") (pinfunction "VSSA_19") (pintype "bidirectional"))
      (node (ref "IC9") (pin "26") (pinfunction "VSS_2_26") (pintype "bidirectional"))
      (node (ref "IC9") (pin "49") (pinfunction "VSS_3_49") (pintype "bidirectional"))
      (node (ref "IC9") (pin "74") (pinfunction "VSS_4_74") (pintype "bidirectional"))
      (node (ref "MEZZANINE") (pin "E13") (pinfunction "E13_E13") (pintype "bidirectional"))
      (node (ref "MEZZANINE") (pin "E14") (pinfunction "E14_E14") (pintype "bidirectional"))
      (node (ref "MEZZANINE") (pin "F10") (pinfunction "F10_F10") (pintype "bidirectional"))
      (node (ref "MEZZANINE") (pin "F11") (pinfunction "F11_F11") (pintype "bidirectional"))
      (node (ref "MEZZANINE") (pin "F12") (pinfunction "F12_F12") (pintype "bidirectional"))
      (node (ref "MEZZANINE") (pin "F19") (pinfunction "F19_F19") (pintype "bidirectional"))
      (node (ref "MEZZANINE") (pin "F7") (pinfunction "F7_F7") (pintype "bidirectional"))
      (node (ref "MEZZANINE") (pin "F8") (pinfunction "F8_F8") (pintype "bidirectional"))
      (node (ref "MEZZANINE") (pin "F9") (pinfunction "F9_F9") (pintype "bidirectional"))
      (node (ref "R6") (pin "2") (pinfunction "2_2") (pintype "passive"))
      (node (ref "RN10") (pin "2") (pinfunction "1_2") (pintype "passive"))
      (node (ref "RN7") (pin "4") (pinfunction "1_4") (pintype "passive"))
      (node (ref "RN8") (pin "5") (pinfunction "2_5") (pintype "passive"))
      (node (ref "RN9") (pin "2") (pinfunction "1_2") (pintype "passive"))
      (node (ref "RN9") (pin "3") (pinfunction "1_3") (pintype "passive"))
      (node (ref "RN9") (pin "4") (pinfunction "1_4") (pintype "passive"))
      (node (ref "RN9") (pin "8") (pinfunction "2_8") (pintype "passive"))
      (node (ref "SD100") (pin "P$10") (pinfunction "SH_P$10") (pintype "passive"))
      (node (ref "SD100") (pin "P$11") (pinfunction "SH_P$11") (pintype "passive"))
      (node (ref "SD100") (pin "P$12") (pinfunction "SH_P$12") (pintype "passive"))
      (node (ref "SD100") (pin "P$13") (pinfunction "SH_P$13") (pintype "passive"))
      (node (ref "SD100") (pin "P$4") (pinfunction "VSS_P$4") (pintype "power_in"))
      (node (ref "TILE1") (pin "0V@1") (pinfunction "0V_0V@1") (pintype "power_in"))
      (node (ref "TILE1") (pin "0V@2") (pinfunction "0V_0V@2") (pintype "power_in"))
      (node (ref "TILE1") (pin "P$1") (pinfunction "V-_P$1") (pintype "power_in"))
      (node (ref "TILE1") (pin "P$2") (pinfunction "V-_P$2") (pintype "power_in"))
      (node (ref "TILE1") (pin "P$26") (pinfunction "V-_P$26") (pintype "power_in"))
      (node (ref "TILE1") (pin "P$27") (pinfunction "V-_P$27") (pintype "power_in"))
      (node (ref "TILE1") (pin "P$28") (pinfunction "V-_P$28") (pintype "power_in"))
      (node (ref "TILE1") (pin "P$29") (pinfunction "V-_P$29") (pintype "power_in"))
      (node (ref "TILE1") (pin "P$3") (pinfunction "V-_P$3") (pintype "power_in"))
      (node (ref "TILE1") (pin "P$30") (pinfunction "V-_P$30") (pintype "power_in"))
      (node (ref "TILE1") (pin "P$31") (pinfunction "V-_P$31") (pintype "power_in"))
      (node (ref "TILE1") (pin "P$32") (pinfunction "GND_P$32") (pintype "power_in"))
      (node (ref "TILE1") (pin "P$4") (pinfunction "V-_P$4") (pintype "power_in"))
      (node (ref "TILE1") (pin "P$5") (pinfunction "V-_P$5") (pintype "power_in"))
      (node (ref "TILE1") (pin "P$6") (pinfunction "V-_P$6") (pintype "power_in"))
      (node (ref "TILE1") (pin "P$7") (pinfunction "GND_P$7") (pintype "power_in"))
      (node (ref "TILE2") (pin "0V@1") (pinfunction "0V_0V@1") (pintype "power_in"))
      (node (ref "TILE2") (pin "0V@2") (pinfunction "0V_0V@2") (pintype "power_in"))
      (node (ref "TILE2") (pin "P$1") (pinfunction "V-_P$1") (pintype "power_in"))
      (node (ref "TILE2") (pin "P$2") (pinfunction "V-_P$2") (pintype "power_in"))
      (node (ref "TILE2") (pin "P$26") (pinfunction "V-_P$26") (pintype "power_in"))
      (node (ref "TILE2") (pin "P$27") (pinfunction "V-_P$27") (pintype "power_in"))
      (node (ref "TILE2") (pin "P$28") (pinfunction "V-_P$28") (pintype "power_in"))
      (node (ref "TILE2") (pin "P$29") (pinfunction "V-_P$29") (pintype "power_in"))
      (node (ref "TILE2") (pin "P$3") (pinfunction "V-_P$3") (pintype "power_in"))
      (node (ref "TILE2") (pin "P$30") (pinfunction "V-_P$30") (pintype "power_in"))
      (node (ref "TILE2") (pin "P$31") (pinfunction "V-_P$31") (pintype "power_in"))
      (node (ref "TILE2") (pin "P$32") (pinfunction "GND_P$32") (pintype "power_in"))
      (node (ref "TILE2") (pin "P$4") (pinfunction "V-_P$4") (pintype "power_in"))
      (node (ref "TILE2") (pin "P$5") (pinfunction "V-_P$5") (pintype "power_in"))
      (node (ref "TILE2") (pin "P$6") (pinfunction "V-_P$6") (pintype "power_in"))
      (node (ref "TILE2") (pin "P$7") (pinfunction "GND_P$7") (pintype "power_in"))
      (node (ref "TILE3") (pin "0V@1") (pinfunction "0V_0V@1") (pintype "power_in"))
      (node (ref "TILE3") (pin "0V@2") (pinfunction "0V_0V@2") (pintype "power_in"))
      (node (ref "TILE3") (pin "P$1") (pinfunction "V-_P$1") (pintype "power_in"))
      (node (ref "TILE3") (pin "P$2") (pinfunction "V-_P$2") (pintype "power_in"))
      (node (ref "TILE3") (pin "P$26") (pinfunction "V-_P$26") (pintype "power_in"))
      (node (ref "TILE3") (pin "P$27") (pinfunction "V-_P$27") (pintype "power_in"))
      (node (ref "TILE3") (pin "P$28") (pinfunction "V-_P$28") (pintype "power_in"))
      (node (ref "TILE3") (pin "P$29") (pinfunction "V-_P$29") (pintype "power_in"))
      (node (ref "TILE3") (pin "P$3") (pinfunction "V-_P$3") (pintype "power_in"))
      (node (ref "TILE3") (pin "P$30") (pinfunction "V-_P$30") (pintype "power_in"))
      (node (ref "TILE3") (pin "P$31") (pinfunction "V-_P$31") (pintype "power_in"))
      (node (ref "TILE3") (pin "P$32") (pinfunction "GND_P$32") (pintype "power_in"))
      (node (ref "TILE3") (pin "P$4") (pinfunction "V-_P$4") (pintype "power_in"))
      (node (ref "TILE3") (pin "P$5") (pinfunction "V-_P$5") (pintype "power_in"))
      (node (ref "TILE3") (pin "P$6") (pinfunction "V-_P$6") (pintype "power_in"))
      (node (ref "TILE3") (pin "P$7") (pinfunction "GND_P$7") (pintype "power_in"))
      (node (ref "TILE4") (pin "0V@1") (pinfunction "0V_0V@1") (pintype "power_in"))
      (node (ref "TILE4") (pin "0V@2") (pinfunction "0V_0V@2") (pintype "power_in"))
      (node (ref "TILE4") (pin "P$1") (pinfunction "V-_P$1") (pintype "power_in"))
      (node (ref "TILE4") (pin "P$2") (pinfunction "V-_P$2") (pintype "power_in"))
      (node (ref "TILE4") (pin "P$26") (pinfunction "V-_P$26") (pintype "power_in"))
      (node (ref "TILE4") (pin "P$27") (pinfunction "V-_P$27") (pintype "power_in"))
      (node (ref "TILE4") (pin "P$28") (pinfunction "V-_P$28") (pintype "power_in"))
      (node (ref "TILE4") (pin "P$29") (pinfunction "V-_P$29") (pintype "power_in"))
      (node (ref "TILE4") (pin "P$3") (pinfunction "V-_P$3") (pintype "power_in"))
      (node (ref "TILE4") (pin "P$30") (pinfunction "V-_P$30") (pintype "power_in"))
      (node (ref "TILE4") (pin "P$31") (pinfunction "V-_P$31") (pintype "power_in"))
      (node (ref "TILE4") (pin "P$32") (pinfunction "GND_P$32") (pintype "power_in"))
      (node (ref "TILE4") (pin "P$4") (pinfunction "V-_P$4") (pintype "power_in"))
      (node (ref "TILE4") (pin "P$5") (pinfunction "V-_P$5") (pintype "power_in"))
      (node (ref "TILE4") (pin "P$6") (pinfunction "V-_P$6") (pintype "power_in"))
      (node (ref "TILE4") (pin "P$7") (pinfunction "GND_P$7") (pintype "power_in"))
      (node (ref "TILE5") (pin "0V@1") (pinfunction "0V_0V@1") (pintype "power_in"))
      (node (ref "TILE5") (pin "0V@2") (pinfunction "0V_0V@2") (pintype "power_in"))
      (node (ref "TILE5") (pin "P$1") (pinfunction "V-_P$1") (pintype "power_in"))
      (node (ref "TILE5") (pin "P$2") (pinfunction "V-_P$2") (pintype "power_in"))
      (node (ref "TILE5") (pin "P$26") (pinfunction "V-_P$26") (pintype "power_in"))
      (node (ref "TILE5") (pin "P$27") (pinfunction "V-_P$27") (pintype "power_in"))
      (node (ref "TILE5") (pin "P$28") (pinfunction "V-_P$28") (pintype "power_in"))
      (node (ref "TILE5") (pin "P$29") (pinfunction "V-_P$29") (pintype "power_in"))
      (node (ref "TILE5") (pin "P$3") (pinfunction "V-_P$3") (pintype "power_in"))
      (node (ref "TILE5") (pin "P$30") (pinfunction "V-_P$30") (pintype "power_in"))
      (node (ref "TILE5") (pin "P$31") (pinfunction "V-_P$31") (pintype "power_in"))
      (node (ref "TILE5") (pin "P$32") (pinfunction "GND_P$32") (pintype "power_in"))
      (node (ref "TILE5") (pin "P$4") (pinfunction "V-_P$4") (pintype "power_in"))
      (node (ref "TILE5") (pin "P$5") (pinfunction "V-_P$5") (pintype "power_in"))
      (node (ref "TILE5") (pin "P$6") (pinfunction "V-_P$6") (pintype "power_in"))
      (node (ref "TILE5") (pin "P$7") (pinfunction "GND_P$7") (pintype "power_in"))
      (node (ref "Y1") (pin "2") (pinfunction "GND_2") (pintype "power_in"))
      (node (ref "Y1") (pin "4") (pinfunction "GND_4") (pintype "passive"))
    )
    (net (code "199") (name "Net-(IC1-FB)") (class "Default")
      (node (ref "C5") (pin "1") (pinfunction "1_1") (pintype "passive"))
      (node (ref "IC1") (pin "5") (pinfunction "FB_5") (pintype "input"))
      (node (ref "RN10") (pin "1") (pinfunction "1_1") (pintype "passive"))
      (node (ref "RN10") (pin "7") (pinfunction "2_7") (pintype "passive"))
    )
    (net (code "200") (name "Net-(IC1-LX)") (class "Default")
      (node (ref "I1") (pin "P$1") (pinfunction "P$1_P$1") (pintype "passive"))
      (node (ref "IC1") (pin "3") (pinfunction "LX_3") (pintype "power_in"))
    )
    (net (code "201") (name "Net-(IC5-FB)") (class "Default")
      (node (ref "C11") (pin "1") (pinfunction "1_1") (pintype "passive"))
      (node (ref "IC5") (pin "5") (pinfunction "FB_5") (pintype "input"))
      (node (ref "R6") (pin "1") (pinfunction "1_1") (pintype "passive"))
      (node (ref "RN10") (pin "4") (pinfunction "1_4") (pintype "passive"))
    )
    (net (code "202") (name "Net-(IC5-LX)") (class "Default")
      (node (ref "I2") (pin "P$1") (pinfunction "P$1_P$1") (pintype "passive"))
      (node (ref "IC5") (pin "3") (pinfunction "LX_3") (pintype "power_in"))
    )
    (net (code "203") (name "Net-(IC9-PC14-OSC32_IN)") (class "Default")
      (node (ref "C28") (pin "2") (pinfunction "2_2") (pintype "passive"))
      (node (ref "IC9") (pin "8") (pinfunction "PC14-OSC32_IN_8") (pintype "bidirectional"))
      (node (ref "Y2") (pin "P$2") (pinfunction "X2_P$2") (pintype "passive"))
    )
    (net (code "204") (name "Net-(IC9-PC15-OSC32_OUT)") (class "Default")
      (node (ref "C26") (pin "2") (pinfunction "2_2") (pintype "passive"))
      (node (ref "IC9") (pin "9") (pinfunction "PC15-OSC32_OUT_9") (pintype "bidirectional"))
      (node (ref "Y2") (pin "P$1") (pinfunction "X1_P$1") (pintype "passive"))
    )
    (net (code "205") (name "Net-(IC9-PH0-OSC_IN)") (class "Default")
      (node (ref "C27") (pin "2") (pinfunction "2_2") (pintype "passive"))
      (node (ref "IC9") (pin "12") (pinfunction "PH0-OSC_IN_12") (pintype "bidirectional"))
      (node (ref "Y1") (pin "1") (pinfunction "X1_1") (pintype "passive"))
    )
    (net (code "206") (name "Net-(IC9-PH1-OSC_OUT)") (class "Default")
      (node (ref "C29") (pin "2") (pinfunction "2_2") (pintype "passive"))
      (node (ref "IC9") (pin "13") (pinfunction "PH1-OSC_OUT_13") (pintype "bidirectional"))
      (node (ref "Y1") (pin "3") (pinfunction "X2_3") (pintype "passive"))
    )
    (net (code "207") (name "Net-(IC9-VCAP1)") (class "Default")
      (node (ref "C18") (pin "2") (pinfunction "2_2") (pintype "passive"))
      (node (ref "IC9") (pin "48") (pinfunction "VCAP1_48") (pintype "bidirectional"))
    )
    (net (code "208") (name "Net-(IC9-VCAP2)") (class "Default")
      (node (ref "C15") (pin "1") (pinfunction "1_1") (pintype "passive"))
      (node (ref "IC9") (pin "73") (pinfunction "VCAP2_73") (pintype "bidirectional"))
    )
    (net (code "209") (name "Net-(IC9-VDDA)") (class "Default")
      (node (ref "C25") (pin "1") (pinfunction "1_1") (pintype "passive"))
      (node (ref "IC9") (pin "20") (pinfunction "VREF+_20") (pintype "bidirectional"))
      (node (ref "IC9") (pin "21") (pinfunction "VDDA_21") (pintype "bidirectional"))
      (node (ref "R7") (pin "1") (pinfunction "1_1") (pintype "passive"))
    )
    (net (code "210") (name "Net-(L1-BC)") (class "Default")
      (node (ref "L1") (pin "B") (pinfunction "BC_B") (pintype "bidirectional"))
      (node (ref "RN8") (pin "3") (pinfunction "1_3") (pintype "passive"))
    )
    (net (code "211") (name "Net-(L1-GC)") (class "Default")
      (node (ref "L1") (pin "G") (pinfunction "GC_G") (pintype "bidirectional"))
      (node (ref "RN8") (pin "2") (pinfunction "1_2") (pintype "passive"))
    )
    (net (code "212") (name "Net-(L1-RC)") (class "Default")
      (node (ref "L1") (pin "R") (pinfunction "RC_R") (pintype "bidirectional"))
      (node (ref "RN8") (pin "1") (pinfunction "1_1") (pintype "passive"))
    )
    (net (code "213") (name "Net-(RN7D-2)") (class "Default")
      (node (ref "L2") (pin "C") (pinfunction "C_C") (pintype "passive"))
      (node (ref "RN7") (pin "5") (pinfunction "2_5") (pintype "passive"))
    )
    (net (code "214") (name "unconnected-(CN1-PadSBU1)") (class "Default")
      (node (ref "CN1") (pin "SBU1") (pinfunction "SBU1_SBU1") (pintype "bidirectional"))
    )
    (net (code "215") (name "unconnected-(CN1-PadSBU2)") (class "Default")
      (node (ref "CN1") (pin "SBU2") (pinfunction "SBU2_SBU2") (pintype "bidirectional"))
    )
    (net (code "216") (name "unconnected-(CN2-PadSBU1)") (class "Default")
      (node (ref "CN2") (pin "SBU1") (pinfunction "SBU1_SBU1") (pintype "bidirectional"))
    )
    (net (code "217") (name "unconnected-(CN2-PadSBU2)") (class "Default")
      (node (ref "CN2") (pin "SBU2") (pinfunction "SBU2_SBU2") (pintype "bidirectional"))
    )
    (net (code "218") (name "unconnected-(CN3-Pad4)") (class "Default")
      (node (ref "CN3") (pin "4") (pinfunction "4_4") (pintype "bidirectional"))
    )
    (net (code "219") (name "unconnected-(CN3-Pad7)") (class "Default")
      (node (ref "CN3") (pin "7") (pinfunction "7_7") (pintype "bidirectional"))
    )
    (net (code "220") (name "unconnected-(IC2-NC-Pad4)") (class "Default")
      (node (ref "IC2") (pin "4") (pinfunction "NC_4") (pintype "no_connect"))
    )
    (net (code "221") (name "unconnected-(IC3-VPP_FAST-PadB10)") (class "Default")
      (node (ref "IC3") (pin "B10") (pinfunction "VPP_FAST_B10") (pintype "bidirectional"))
    )
    (net (code "222") (name "unconnected-(IC7-I{slash}O1_2-Pad6)") (class "Default")
      (node (ref "IC7") (pin "6") (pinfunction "I/O1_2_6") (pintype "bidirectional"))
    )
    (net (code "223") (name "unconnected-(IC7-I{slash}O2_2-Pad4)") (class "Default")
      (node (ref "IC7") (pin "4") (pinfunction "I/O2_2_4") (pintype "bidirectional"))
    )
    (net (code "224") (name "unconnected-(IC8-I{slash}O1_1-Pad1)") (class "Default")
      (node (ref "IC8") (pin "1") (pinfunction "I/O1_1_1") (pintype "bidirectional"))
    )
    (net (code "225") (name "unconnected-(IC8-I{slash}O2_1-Pad3)") (class "Default")
      (node (ref "IC8") (pin "3") (pinfunction "I/O2_1_3") (pintype "bidirectional"))
    )
    (net (code "226") (name "unconnected-(IC9-VDD_1-Pad11)") (class "Default")
      (node (ref "IC9") (pin "11") (pinfunction "VDD_1_11") (pintype "bidirectional"))
    )
    (net (code "227") (name "unconnected-(IC9-VSS_1-Pad10)") (class "Default")
      (node (ref "IC9") (pin "10") (pinfunction "VSS_1_10") (pintype "bidirectional"))
    )
    (net (code "228") (name "unconnected-(IC9-VSS_5-Pad99)") (class "Default")
      (node (ref "IC9") (pin "99") (pinfunction "VSS_5_99") (pintype "bidirectional"))
    )
    (net (code "229") (name "unconnected-(IC10-N{slash}C-Pad15)") (class "Default")
      (node (ref "IC10") (pin "15") (pinfunction "N/C_15") (pintype "no_connect"))
    )
    (net (code "230") (name "unconnected-(MEZZANINE-PadF6)") (class "Default")
      (node (ref "MEZZANINE") (pin "F6") (pinfunction "F6_F6") (pintype "bidirectional"))
    )
    (net (code "231") (name "unconnected-(RN10C-1-Pad3)") (class "Default")
      (node (ref "RN10") (pin "3") (pinfunction "1_3") (pintype "passive"))
    )
    (net (code "232") (name "unconnected-(RN10C-2-Pad6)") (class "Default")
      (node (ref "RN10") (pin "6") (pinfunction "2_6") (pintype "passive"))
    )
  )
)
